# 15.net
KiCad netlist of a schematic drawn in EasyEDA Pro
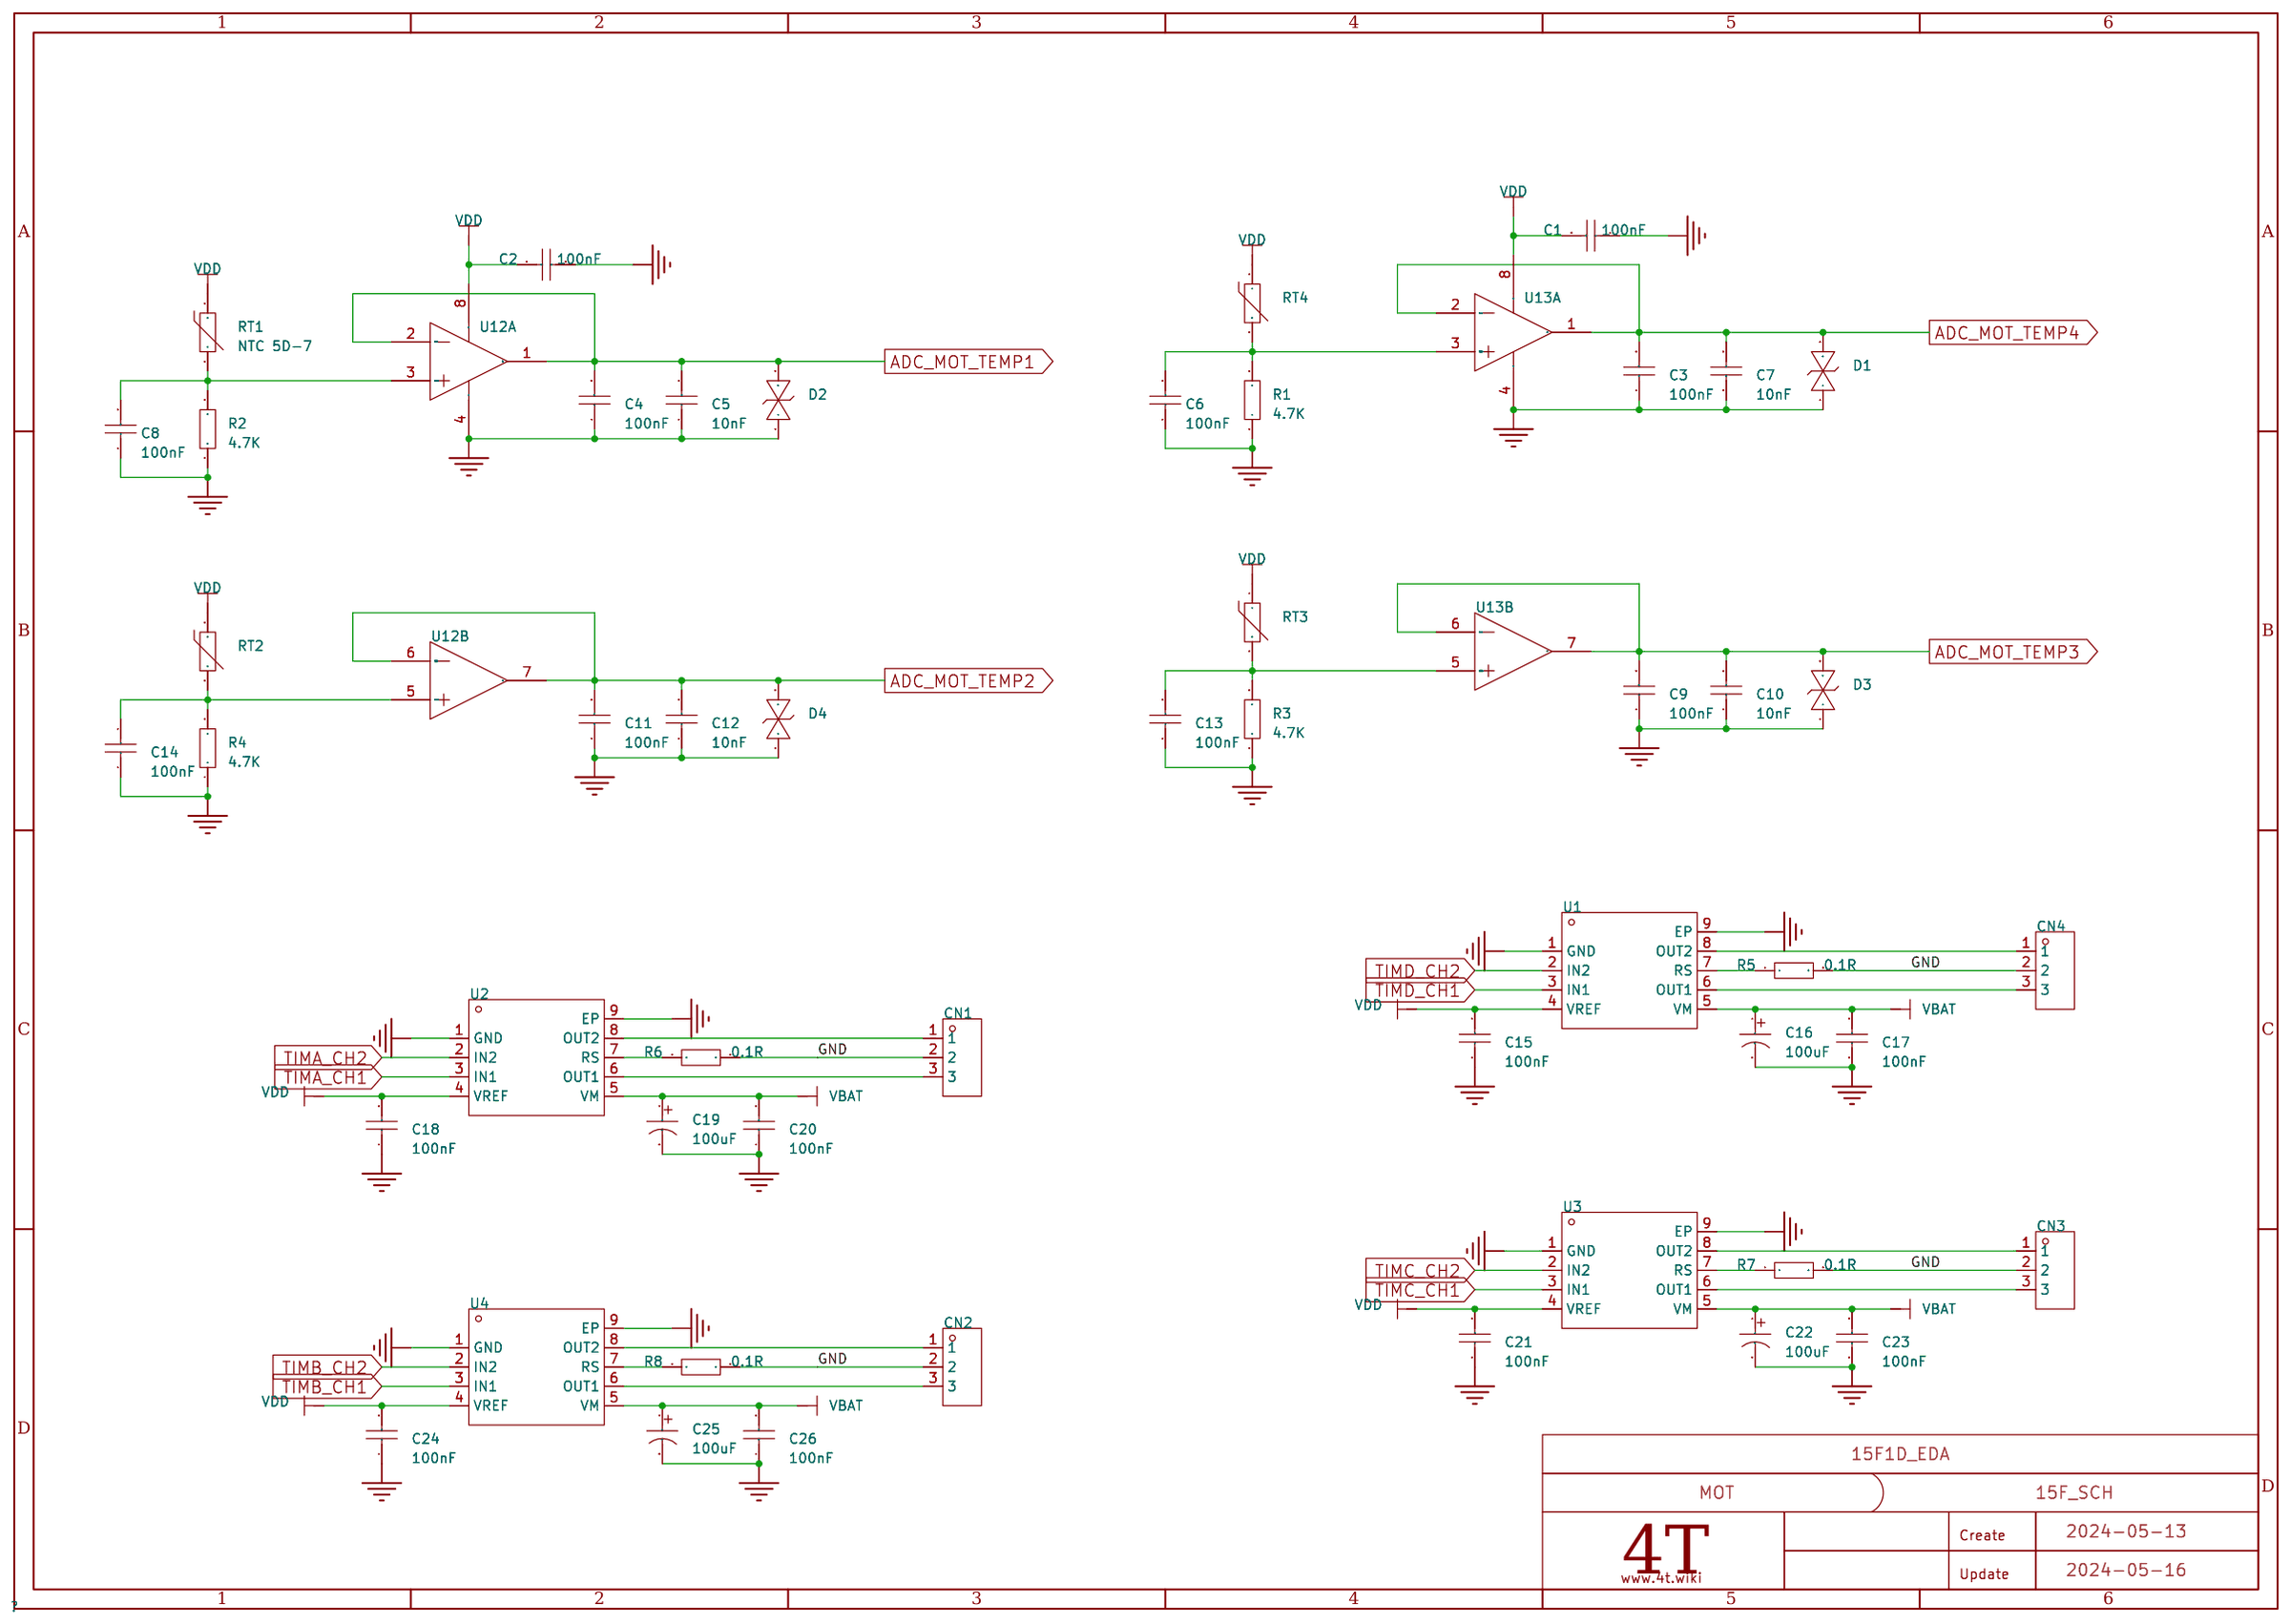
[diagram p0: MOT]
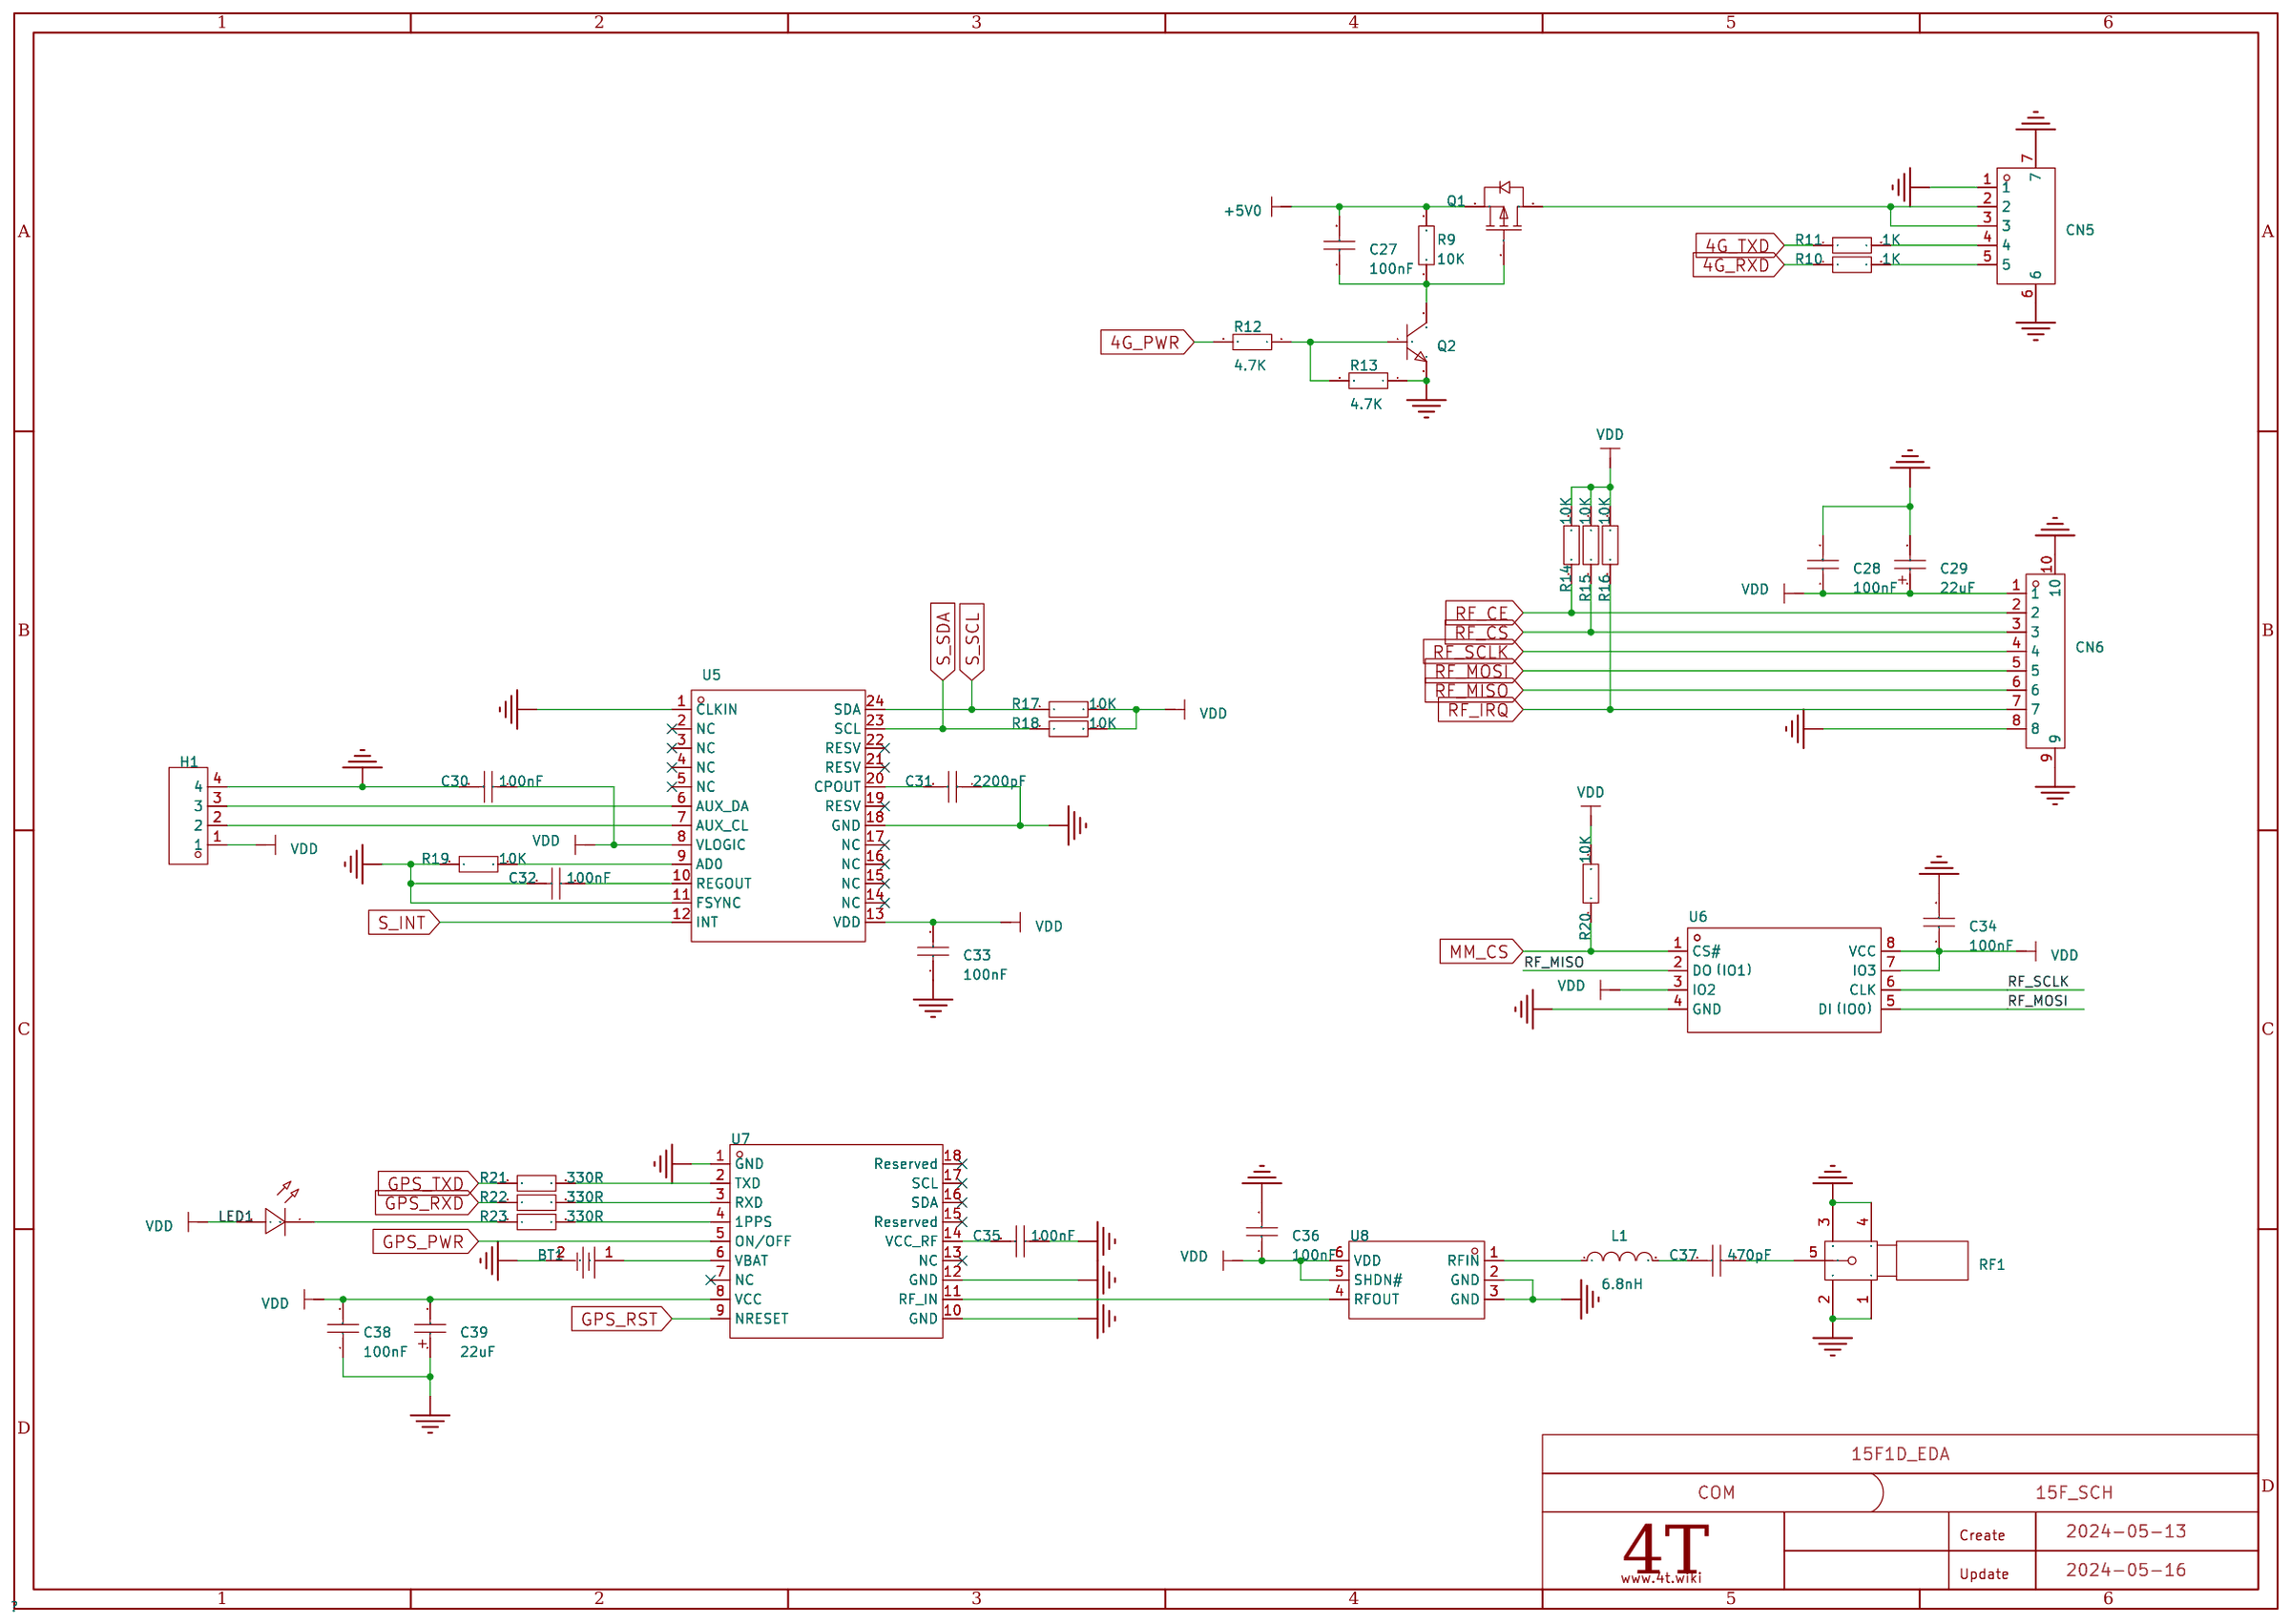
[diagram p1: COM]
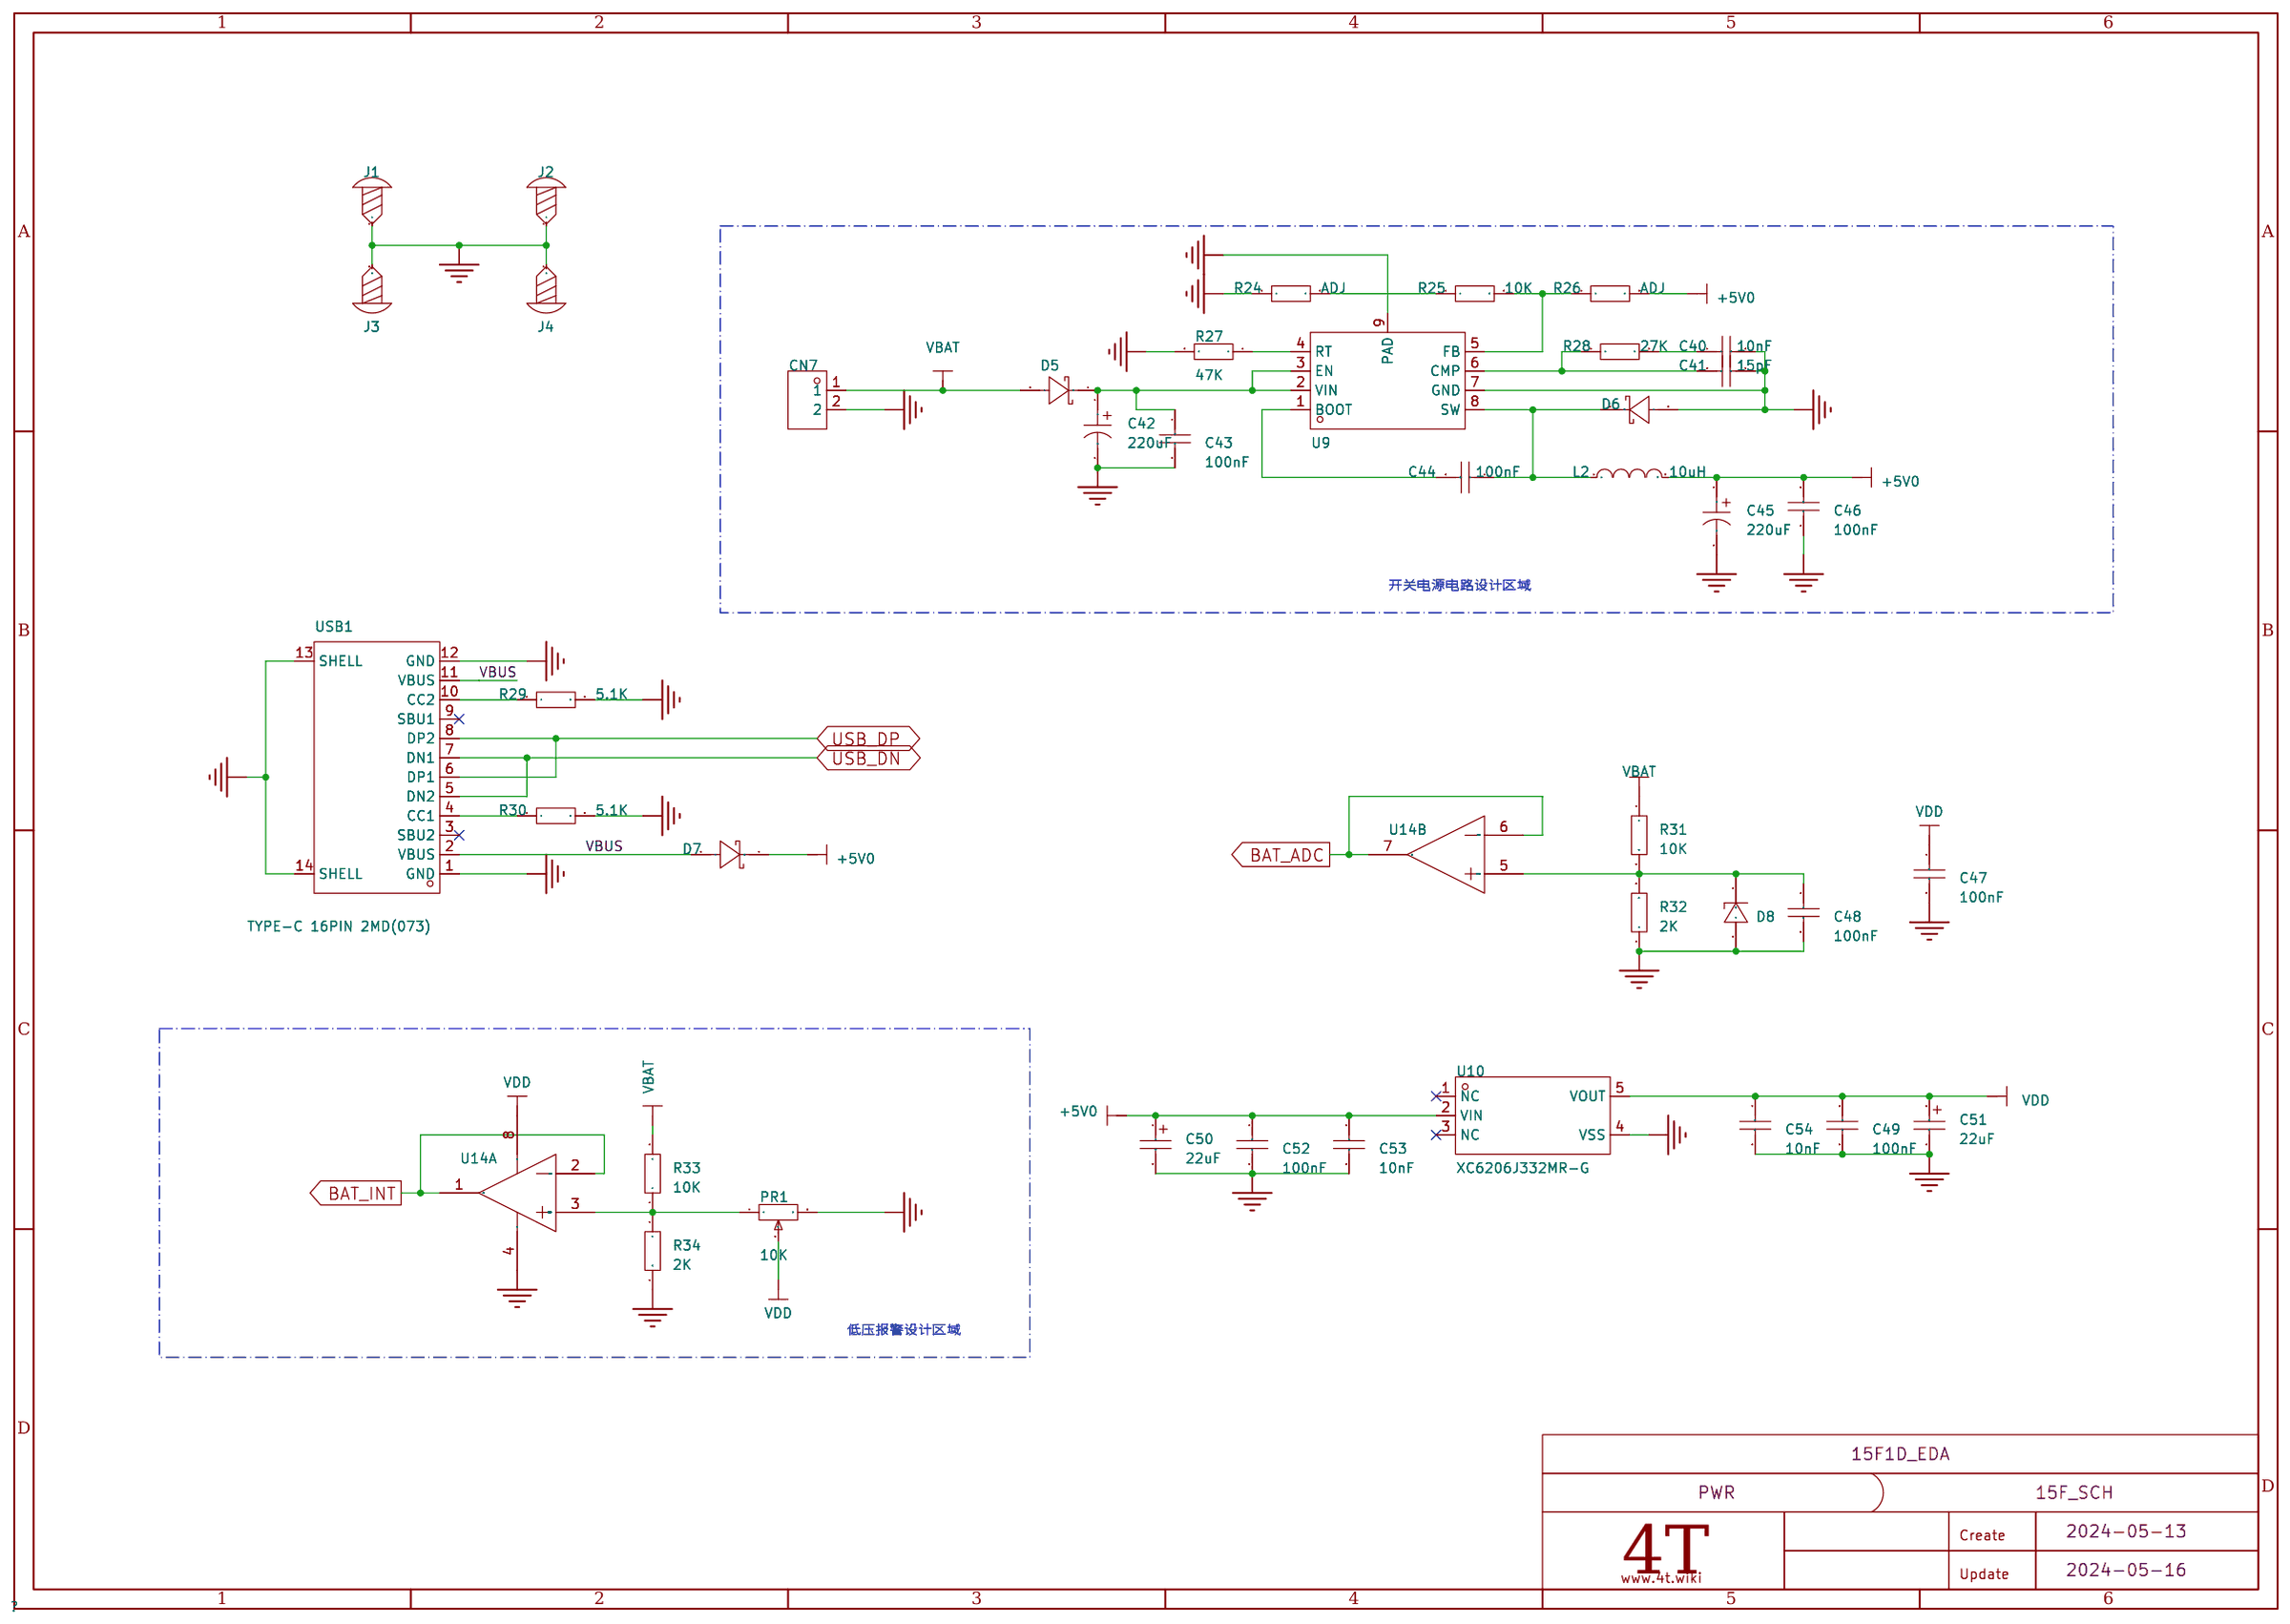
[diagram p2: PWR]
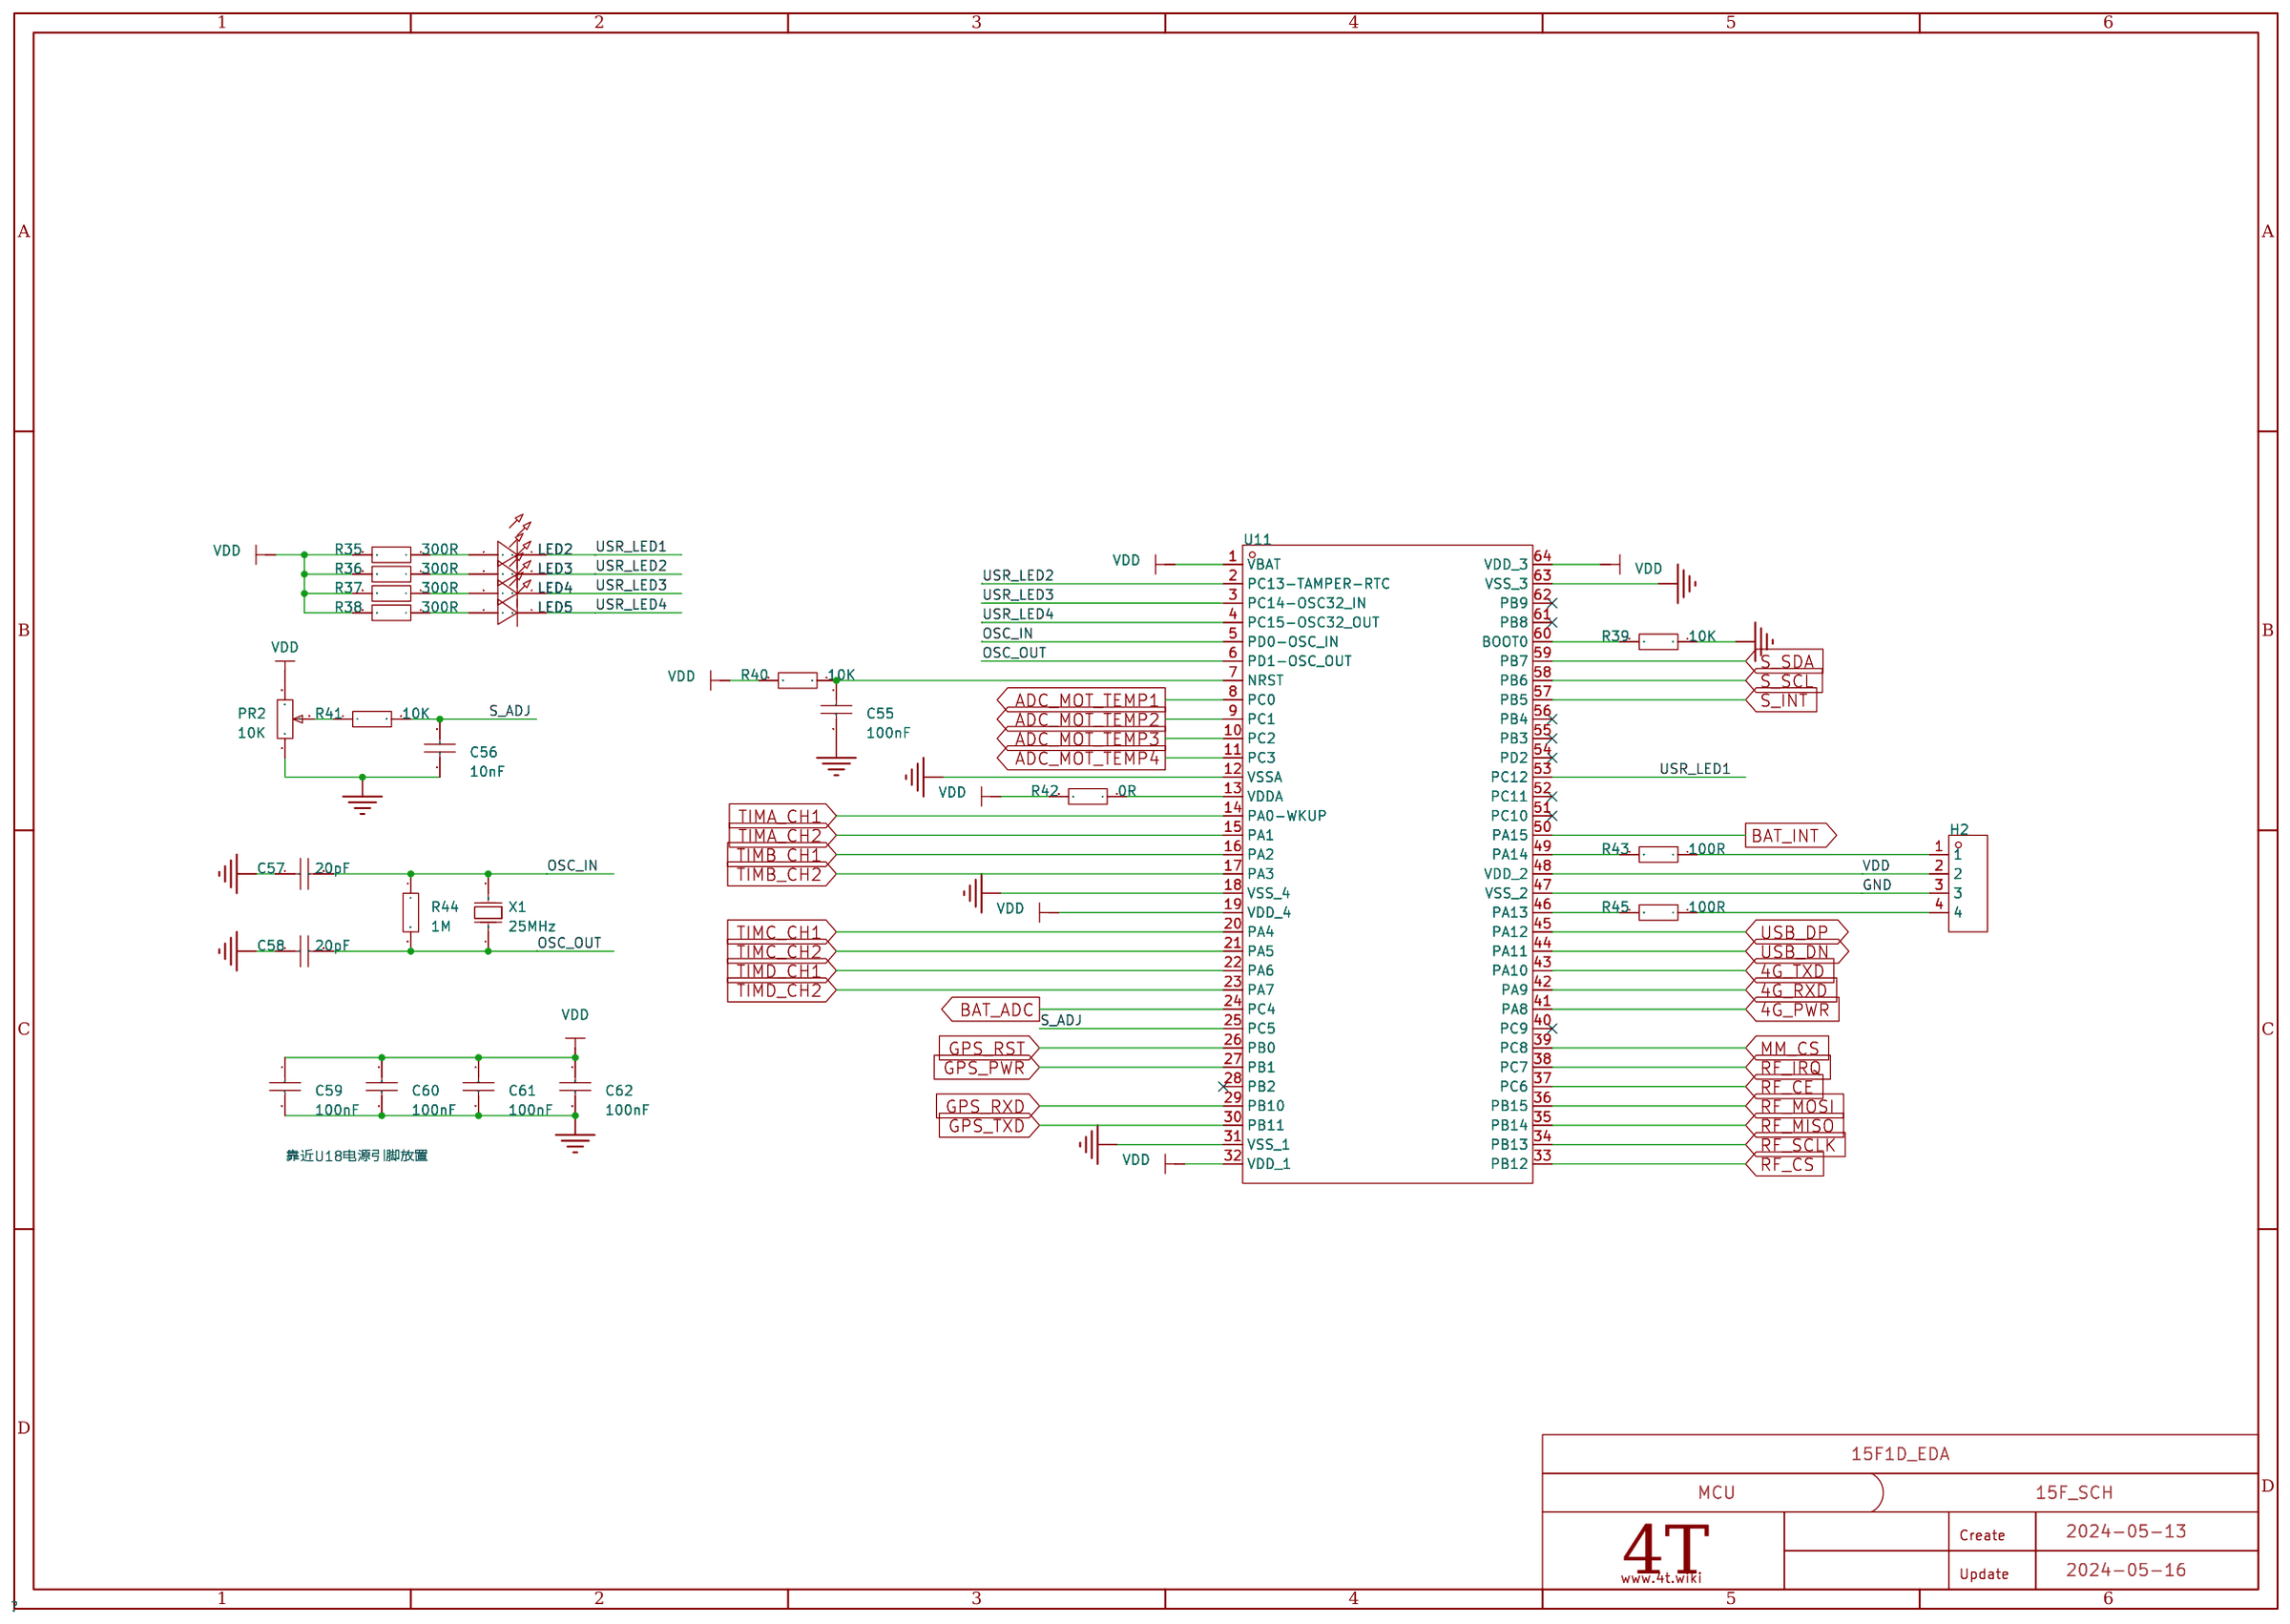
[diagram p3: MCU]

(export (version "E")
  (design (tool "Eeschema 10.0.6"))
  (components
    (comp (ref "C1")
      (value "100nF")
      (footprint "easyedapro:C0805")
      (description "容值:100nF;精度:±10%;额定电压:100V;材质(温度系数):X7R;")
      (fields
        (field (name "Manufacturer Part") "CC0805KKX7R0BB104")
        (field (name "Manufacturer") "YAGEO(国巨)")
      )
      (libsource (lib "easyedapro") (part "CC0805KKX7R0BB104"))
    )
    (comp (ref "C2")
      (value "100nF")
      (footprint "easyedapro:C0805")
      (description "容值:100nF;精度:±10%;额定电压:100V;材质(温度系数):X7R;")
      (fields
        (field (name "Manufacturer Part") "CC0805KKX7R0BB104")
        (field (name "Manufacturer") "YAGEO(国巨)")
      )
      (libsource (lib "easyedapro") (part "CC0805KKX7R0BB104"))
    )
    (comp (ref "C3")
      (value "100nF")
      (footprint "easyedapro:C0805")
      (description "容值:100nF;精度:±10%;额定电压:100V;材质(温度系数):X7R;")
      (fields
        (field (name "Manufacturer Part") "CC0805KKX7R0BB104")
        (field (name "Manufacturer") "YAGEO(国巨)")
      )
      (libsource (lib "easyedapro") (part "CC0805KKX7R0BB104"))
    )
    (comp (ref "C4")
      (value "100nF")
      (footprint "easyedapro:C0805")
      (description "容值:100nF;精度:±10%;额定电压:100V;材质(温度系数):X7R;")
      (fields
        (field (name "Manufacturer Part") "CC0805KKX7R0BB104")
        (field (name "Manufacturer") "YAGEO(国巨)")
      )
      (libsource (lib "easyedapro") (part "CC0805KKX7R0BB104"))
    )
    (comp (ref "C5")
      (value "10nF")
      (footprint "easyedapro:C0805")
      (description "容值:100nF;精度:±10%;额定电压:100V;材质(温度系数):X7R;")
      (fields
        (field (name "Manufacturer Part") "CC0805KKX7R0BB104")
        (field (name "Manufacturer") "YAGEO(国巨)")
      )
      (libsource (lib "easyedapro") (part "CC0805KKX7R0BB104"))
    )
    (comp (ref "C6")
      (value "100nF")
      (footprint "easyedapro:C0805")
      (description "容值:100nF;精度:±10%;额定电压:100V;材质(温度系数):X7R;")
      (fields
        (field (name "Manufacturer Part") "CC0805KKX7R0BB104")
        (field (name "Manufacturer") "YAGEO(国巨)")
      )
      (libsource (lib "easyedapro") (part "CC0805KKX7R0BB104"))
    )
    (comp (ref "C7")
      (value "10nF")
      (footprint "easyedapro:C0805")
      (description "容值:100nF;精度:±10%;额定电压:100V;材质(温度系数):X7R;")
      (fields
        (field (name "Manufacturer Part") "CC0805KKX7R0BB104")
        (field (name "Manufacturer") "YAGEO(国巨)")
      )
      (libsource (lib "easyedapro") (part "CC0805KKX7R0BB104"))
    )
    (comp (ref "C8")
      (value "100nF")
      (footprint "easyedapro:C0805")
      (description "容值:100nF;精度:±10%;额定电压:100V;材质(温度系数):X7R;")
      (fields
        (field (name "Manufacturer Part") "CC0805KKX7R0BB104")
        (field (name "Manufacturer") "YAGEO(国巨)")
      )
      (libsource (lib "easyedapro") (part "CC0805KKX7R0BB104"))
    )
    (comp (ref "C9")
      (value "100nF")
      (footprint "easyedapro:C0805")
      (description "容值:100nF;精度:±10%;额定电压:100V;材质(温度系数):X7R;")
      (fields
        (field (name "Manufacturer Part") "CC0805KKX7R0BB104")
        (field (name "Manufacturer") "YAGEO(国巨)")
      )
      (libsource (lib "easyedapro") (part "CC0805KKX7R0BB104"))
    )
    (comp (ref "C10")
      (value "10nF")
      (footprint "easyedapro:C0805")
      (description "容值:100nF;精度:±10%;额定电压:100V;材质(温度系数):X7R;")
      (fields
        (field (name "Manufacturer Part") "CC0805KKX7R0BB104")
        (field (name "Manufacturer") "YAGEO(国巨)")
      )
      (libsource (lib "easyedapro") (part "CC0805KKX7R0BB104"))
    )
    (comp (ref "C11")
      (value "100nF")
      (footprint "easyedapro:C0805")
      (description "容值:100nF;精度:±10%;额定电压:100V;材质(温度系数):X7R;")
      (fields
        (field (name "Manufacturer Part") "CC0805KKX7R0BB104")
        (field (name "Manufacturer") "YAGEO(国巨)")
      )
      (libsource (lib "easyedapro") (part "CC0805KKX7R0BB104"))
    )
    (comp (ref "C12")
      (value "10nF")
      (footprint "easyedapro:C0805")
      (description "容值:100nF;精度:±10%;额定电压:100V;材质(温度系数):X7R;")
      (fields
        (field (name "Manufacturer Part") "CC0805KKX7R0BB104")
        (field (name "Manufacturer") "YAGEO(国巨)")
      )
      (libsource (lib "easyedapro") (part "CC0805KKX7R0BB104"))
    )
    (comp (ref "C13")
      (value "100nF")
      (footprint "easyedapro:C0805")
      (description "容值:100nF;精度:±10%;额定电压:100V;材质(温度系数):X7R;")
      (fields
        (field (name "Manufacturer Part") "CC0805KKX7R0BB104")
        (field (name "Manufacturer") "YAGEO(国巨)")
      )
      (libsource (lib "easyedapro") (part "CC0805KKX7R0BB104"))
    )
    (comp (ref "C14")
      (value "100nF")
      (footprint "easyedapro:C0805")
      (description "容值:100nF;精度:±10%;额定电压:100V;材质(温度系数):X7R;")
      (fields
        (field (name "Manufacturer Part") "CC0805KKX7R0BB104")
        (field (name "Manufacturer") "YAGEO(国巨)")
      )
      (libsource (lib "easyedapro") (part "CC0805KKX7R0BB104"))
    )
    (comp (ref "C15")
      (value "100nF")
      (footprint "easyedapro:C0805")
      (description "容值:100nF;精度:±10%;额定电压:100V;材质(温度系数):X7R;")
      (fields
        (field (name "Manufacturer Part") "CC0805KKX7R0BB104")
        (field (name "Manufacturer") "YAGEO(国巨)")
      )
      (libsource (lib "easyedapro") (part "CC0805KKX7R0BB104"))
    )
    (comp (ref "C16")
      (value "100uF")
      (footprint "easyedapro:CAP-SMD_BD6.3-L6.6-W6.6-LS7.2-FD")
      (description "容值:100uF;精度:±20%;额定电压:16V;纹波电流:-;等效串联电阻:-;")
      (fields (field (name "Manufacturer Part") "RVT1C101M0605") (field (name "Manufacturer") "HONOR(荣誉)"))
      (libsource (lib "easyedapro") (part "RVT1C101M0605"))
    )
    (comp (ref "C17")
      (value "100nF")
      (footprint "easyedapro:C0805")
      (description "容值:100nF;精度:±10%;额定电压:100V;材质(温度系数):X7R;")
      (fields
        (field (name "Manufacturer Part") "CC0805KKX7R0BB104")
        (field (name "Manufacturer") "YAGEO(国巨)")
      )
      (libsource (lib "easyedapro") (part "CC0805KKX7R0BB104"))
    )
    (comp (ref "C18")
      (value "100nF")
      (footprint "easyedapro:C0805")
      (description "容值:100nF;精度:±10%;额定电压:100V;材质(温度系数):X7R;")
      (fields
        (field (name "Manufacturer Part") "CC0805KKX7R0BB104")
        (field (name "Manufacturer") "YAGEO(国巨)")
      )
      (libsource (lib "easyedapro") (part "CC0805KKX7R0BB104"))
    )
    (comp (ref "C19")
      (value "100uF")
      (footprint "easyedapro:CAP-SMD_BD6.3-L6.6-W6.6-LS7.2-FD")
      (description "容值:100uF;精度:±20%;额定电压:16V;纹波电流:-;等效串联电阻:-;")
      (fields (field (name "Manufacturer Part") "RVT1C101M0605") (field (name "Manufacturer") "HONOR(荣誉)"))
      (libsource (lib "easyedapro") (part "RVT1C101M0605"))
    )
    (comp (ref "C20")
      (value "100nF")
      (footprint "easyedapro:C0805")
      (description "容值:100nF;精度:±10%;额定电压:100V;材质(温度系数):X7R;")
      (fields
        (field (name "Manufacturer Part") "CC0805KKX7R0BB104")
        (field (name "Manufacturer") "YAGEO(国巨)")
      )
      (libsource (lib "easyedapro") (part "CC0805KKX7R0BB104"))
    )
    (comp (ref "C21")
      (value "100nF")
      (footprint "easyedapro:C0805")
      (description "容值:100nF;精度:±10%;额定电压:100V;材质(温度系数):X7R;")
      (fields
        (field (name "Manufacturer Part") "CC0805KKX7R0BB104")
        (field (name "Manufacturer") "YAGEO(国巨)")
      )
      (libsource (lib "easyedapro") (part "CC0805KKX7R0BB104"))
    )
    (comp (ref "C22")
      (value "100uF")
      (footprint "easyedapro:CAP-SMD_BD6.3-L6.6-W6.6-LS7.2-FD")
      (description "容值:100uF;精度:±20%;额定电压:16V;纹波电流:-;等效串联电阻:-;")
      (fields (field (name "Manufacturer Part") "RVT1C101M0605") (field (name "Manufacturer") "HONOR(荣誉)"))
      (libsource (lib "easyedapro") (part "RVT1C101M0605"))
    )
    (comp (ref "C23")
      (value "100nF")
      (footprint "easyedapro:C0805")
      (description "容值:100nF;精度:±10%;额定电压:100V;材质(温度系数):X7R;")
      (fields
        (field (name "Manufacturer Part") "CC0805KKX7R0BB104")
        (field (name "Manufacturer") "YAGEO(国巨)")
      )
      (libsource (lib "easyedapro") (part "CC0805KKX7R0BB104"))
    )
    (comp (ref "C24")
      (value "100nF")
      (footprint "easyedapro:C0805")
      (description "容值:100nF;精度:±10%;额定电压:100V;材质(温度系数):X7R;")
      (fields
        (field (name "Manufacturer Part") "CC0805KKX7R0BB104")
        (field (name "Manufacturer") "YAGEO(国巨)")
      )
      (libsource (lib "easyedapro") (part "CC0805KKX7R0BB104"))
    )
    (comp (ref "C25")
      (value "100uF")
      (footprint "easyedapro:CAP-SMD_BD6.3-L6.6-W6.6-LS7.2-FD")
      (description "容值:100uF;精度:±20%;额定电压:16V;纹波电流:-;等效串联电阻:-;")
      (fields (field (name "Manufacturer Part") "RVT1C101M0605") (field (name "Manufacturer") "HONOR(荣誉)"))
      (libsource (lib "easyedapro") (part "RVT1C101M0605"))
    )
    (comp (ref "C26")
      (value "100nF")
      (footprint "easyedapro:C0805")
      (description "容值:100nF;精度:±10%;额定电压:100V;材质(温度系数):X7R;")
      (fields
        (field (name "Manufacturer Part") "CC0805KKX7R0BB104")
        (field (name "Manufacturer") "YAGEO(国巨)")
      )
      (libsource (lib "easyedapro") (part "CC0805KKX7R0BB104"))
    )
    (comp (ref "CN1")
      (value "2.54-1*3P")
      (footprint "easyedapro:CONN-TH_C722693")
      (description "插针结构:1x3P;间距:2.5mm;安装方式:直插;参考系列:-;总PIN数:3P;排数:1;每排PIN数:3;行距:-;额定电流:2A;工作温度范围:-25°C~+85°C;")
      (fields (field (name "Manufacturer") "CAX(创都)"))
      (libsource (lib "easyedapro") (part "2.54-1*3P"))
    )
    (comp (ref "CN2")
      (value "2.54-1*3P")
      (footprint "easyedapro:CONN-TH_C722693")
      (description "插针结构:1x3P;间距:2.5mm;安装方式:直插;参考系列:-;总PIN数:3P;排数:1;每排PIN数:3;行距:-;额定电流:2A;工作温度范围:-25°C~+85°C;")
      (fields (field (name "Manufacturer") "CAX(创都)"))
      (libsource (lib "easyedapro") (part "2.54-1*3P"))
    )
    (comp (ref "CN3")
      (value "2.54-1*3P")
      (footprint "easyedapro:CONN-TH_C722693")
      (description "插针结构:1x3P;间距:2.5mm;安装方式:直插;参考系列:-;总PIN数:3P;排数:1;每排PIN数:3;行距:-;额定电流:2A;工作温度范围:-25°C~+85°C;")
      (fields (field (name "Manufacturer") "CAX(创都)"))
      (libsource (lib "easyedapro") (part "2.54-1*3P"))
    )
    (comp (ref "CN4")
      (value "2.54-1*3P")
      (footprint "easyedapro:CONN-TH_C722693")
      (description "插针结构:1x3P;间距:2.5mm;安装方式:直插;参考系列:-;总PIN数:3P;排数:1;每排PIN数:3;行距:-;额定电流:2A;工作温度范围:-25°C~+85°C;")
      (fields (field (name "Manufacturer") "CAX(创都)"))
      (libsource (lib "easyedapro") (part "2.54-1*3P"))
    )
    (comp (ref "D1")
      (value "H3V3LD5B")
      (footprint "easyedapro:SOD-523F_L1.7-W0.9-LS1.7-BI")
      (description "极性:双向;反向截止电压(Vrwm):3.3V;最大钳位电压:12V;峰值脉冲电流(Ipp)@10/1000us:8A;峰值脉冲功率(Ppp)@10/1000us:100W;击穿电压:6.5V;")
      (fields (field (name "Manufacturer") "宏迦橙"))
      (libsource (lib "easyedapro") (part "H3V3LD5B"))
    )
    (comp (ref "D2")
      (value "H3V3LD5B")
      (footprint "easyedapro:SOD-523F_L1.7-W0.9-LS1.7-BI")
      (description "极性:双向;反向截止电压(Vrwm):3.3V;最大钳位电压:12V;峰值脉冲电流(Ipp)@10/1000us:8A;峰值脉冲功率(Ppp)@10/1000us:100W;击穿电压:6.5V;")
      (fields (field (name "Manufacturer") "宏迦橙"))
      (libsource (lib "easyedapro") (part "H3V3LD5B"))
    )
    (comp (ref "D3")
      (value "H3V3LD5B")
      (footprint "easyedapro:SOD-523F_L1.7-W0.9-LS1.7-BI")
      (description "极性:双向;反向截止电压(Vrwm):3.3V;最大钳位电压:12V;峰值脉冲电流(Ipp)@10/1000us:8A;峰值脉冲功率(Ppp)@10/1000us:100W;击穿电压:6.5V;")
      (fields (field (name "Manufacturer") "宏迦橙"))
      (libsource (lib "easyedapro") (part "H3V3LD5B"))
    )
    (comp (ref "D4")
      (value "H3V3LD5B")
      (footprint "easyedapro:SOD-523F_L1.7-W0.9-LS1.7-BI")
      (description "极性:双向;反向截止电压(Vrwm):3.3V;最大钳位电压:12V;峰值脉冲电流(Ipp)@10/1000us:8A;峰值脉冲功率(Ppp)@10/1000us:100W;击穿电压:6.5V;")
      (fields (field (name "Manufacturer") "宏迦橙"))
      (libsource (lib "easyedapro") (part "H3V3LD5B"))
    )
    (comp (ref "R1") (value "4.7K") (footprint "easyedapro:R0603") (libsource (lib "easyedapro") (part "电阻")))
    (comp (ref "R2") (value "4.7K") (footprint "easyedapro:R0603") (libsource (lib "easyedapro") (part "电阻")))
    (comp (ref "R3") (value "4.7K") (footprint "easyedapro:R0603") (libsource (lib "easyedapro") (part "电阻")))
    (comp (ref "R4") (value "4.7K") (footprint "easyedapro:R0603") (libsource (lib "easyedapro") (part "电阻")))
    (comp (ref "R5") (value "0.1R") (footprint "easyedapro:R0603") (libsource (lib "easyedapro") (part "电阻")))
    (comp (ref "R6") (value "0.1R") (footprint "easyedapro:R0603") (libsource (lib "easyedapro") (part "电阻")))
    (comp (ref "R7") (value "0.1R") (footprint "easyedapro:R0603") (libsource (lib "easyedapro") (part "电阻")))
    (comp (ref "R8") (value "0.1R") (footprint "easyedapro:R0603") (libsource (lib "easyedapro") (part "电阻")))
    (comp (ref "RT1")
      (value "NTC 5D-7")
      (footprint "easyedapro:RES-TH_L8.5-W5.5-P5.00-D0.6-S5.50")
      (description "阻值(25°C):5Ω;B值(25°C/50°C):-;电阻精度:-;功率:-;B值精度:-;最大稳态电流(25°C):2A;")
      (fields (field (name "Manufacturer") "RUILON(瑞隆源)"))
      (libsource (lib "easyedapro") (part "NTC 5D-7"))
    )
    (comp (ref "RT2")
      (value "NTC 5D-7")
      (footprint "easyedapro:RES-TH_L8.5-W5.5-P5.00-D0.6-S5.50")
      (description "阻值(25°C):5Ω;B值(25°C/50°C):-;电阻精度:-;功率:-;B值精度:-;最大稳态电流(25°C):2A;")
      (fields (field (name "Manufacturer") "RUILON(瑞隆源)"))
      (libsource (lib "easyedapro") (part "NTC 5D-7"))
    )
    (comp (ref "RT3")
      (value "NTC 5D-7")
      (footprint "easyedapro:RES-TH_L8.5-W5.5-P5.00-D0.6-S5.50")
      (description "阻值(25°C):5Ω;B值(25°C/50°C):-;电阻精度:-;功率:-;B值精度:-;最大稳态电流(25°C):2A;")
      (fields (field (name "Manufacturer") "RUILON(瑞隆源)"))
      (libsource (lib "easyedapro") (part "NTC 5D-7"))
    )
    (comp (ref "RT4")
      (value "NTC 5D-7")
      (footprint "easyedapro:RES-TH_L8.5-W5.5-P5.00-D0.6-S5.50")
      (description "阻值(25°C):5Ω;B值(25°C/50°C):-;电阻精度:-;功率:-;B值精度:-;最大稳态电流(25°C):2A;")
      (fields (field (name "Manufacturer") "RUILON(瑞隆源)"))
      (libsource (lib "easyedapro") (part "NTC 5D-7"))
    )
    (comp (ref "U1")
      (value "TB67H450FNG,EL")
      (footprint "easyedapro:HSOP-8_L5.0-W4.0-P1.27-LS6.2-BL-EP")
      (description "驱动电机类型:有刷直流电机;输出电流:3.5A;")
      (fields (field (name "Manufacturer") "TOSHIBA(东芝)"))
      (libsource (lib "easyedapro") (part "TB67H450FNG,EL"))
    )
    (comp (ref "U2")
      (value "TB67H450FNG,EL")
      (footprint "easyedapro:HSOP-8_L5.0-W4.0-P1.27-LS6.2-BL-EP")
      (description "驱动电机类型:有刷直流电机;输出电流:3.5A;")
      (fields (field (name "Manufacturer") "TOSHIBA(东芝)"))
      (libsource (lib "easyedapro") (part "TB67H450FNG,EL"))
    )
    (comp (ref "U3")
      (value "TB67H450FNG,EL")
      (footprint "easyedapro:HSOP-8_L5.0-W4.0-P1.27-LS6.2-BL-EP")
      (description "驱动电机类型:有刷直流电机;输出电流:3.5A;")
      (fields (field (name "Manufacturer") "TOSHIBA(东芝)"))
      (libsource (lib "easyedapro") (part "TB67H450FNG,EL"))
    )
    (comp (ref "U4")
      (value "TB67H450FNG,EL")
      (footprint "easyedapro:HSOP-8_L5.0-W4.0-P1.27-LS6.2-BL-EP")
      (description "驱动电机类型:有刷直流电机;输出电流:3.5A;")
      (fields (field (name "Manufacturer") "TOSHIBA(东芝)"))
      (libsource (lib "easyedapro") (part "TB67H450FNG,EL"))
    )
    (comp (ref "U12")
      (value "GS8552-SR")
      (footprint "easyedapro:SOIC-8_L4.9-W3.9-P1.27-LS6.0-BL")
      (description "放大器数:双路;增益带宽积(GBP):1.8MHz;压摆率(SR):0.95V/us;")
      (fields (field (name "Manufacturer") "Gainsil(聚洵)"))
      (libsource (lib "easyedapro") (part "GS8552-SR"))
    )
    (comp (ref "U13")
      (value "GS8552-SR")
      (footprint "easyedapro:SOIC-8_L4.9-W3.9-P1.27-LS6.0-BL")
      (description "放大器数:双路;增益带宽积(GBP):1.8MHz;压摆率(SR):0.95V/us;")
      (fields (field (name "Manufacturer") "Gainsil(聚洵)"))
      (libsource (lib "easyedapro") (part "GS8552-SR"))
    )
    (comp (ref "BT1")
      (value "CR1220-A")
      (footprint "easyedapro:BAT-SMD_CR1220-2")
      (libsource (lib "easyedapro") (part "CR1220-A"))
    )
    (comp (ref "C27")
      (value "100nF")
      (footprint "easyedapro:C0805")
      (description "容值:100nF;精度:±10%;额定电压:100V;材质(温度系数):X7R;")
      (fields
        (field (name "Manufacturer Part") "CC0805KKX7R0BB104")
        (field (name "Manufacturer") "YAGEO(国巨)")
      )
      (libsource (lib "easyedapro") (part "CC0805KKX7R0BB104"))
    )
    (comp (ref "C28")
      (value "100nF")
      (footprint "easyedapro:C0805")
      (description "容值:100nF;精度:±10%;额定电压:100V;材质(温度系数):X7R;")
      (fields
        (field (name "Manufacturer Part") "CC0805KKX7R0BB104")
        (field (name "Manufacturer") "YAGEO(国巨)")
      )
      (libsource (lib "easyedapro") (part "CC0805KKX7R0BB104"))
    )
    (comp (ref "C29")
      (value "22uF")
      (footprint "easyedapro:CASE-A_3216")
      (description "容值:22uF;精度:±10%;额定电压:10V;等效串联电阻:3Ω@100kHz;")
      (fields (field (name "Manufacturer Part") "TAJA226K010RNJ") (field (name "Manufacturer") "Kyocera AVX"))
      (libsource (lib "easyedapro") (part "TAJA226K010RNJ"))
    )
    (comp (ref "C30")
      (value "100nF")
      (footprint "easyedapro:C0805")
      (description "容值:100nF;精度:±10%;额定电压:100V;材质(温度系数):X7R;")
      (fields
        (field (name "Manufacturer Part") "CC0805KKX7R0BB104")
        (field (name "Manufacturer") "YAGEO(国巨)")
      )
      (libsource (lib "easyedapro") (part "CC0805KKX7R0BB104"))
    )
    (comp (ref "C31")
      (value "2200pF")
      (footprint "easyedapro:C0805")
      (description "容值:100nF;精度:±10%;额定电压:100V;材质(温度系数):X7R;")
      (fields
        (field (name "Manufacturer Part") "CC0805KKX7R0BB104")
        (field (name "Manufacturer") "YAGEO(国巨)")
      )
      (libsource (lib "easyedapro") (part "CC0805KKX7R0BB104"))
    )
    (comp (ref "C32")
      (value "100nF")
      (footprint "easyedapro:C0805")
      (description "容值:100nF;精度:±10%;额定电压:100V;材质(温度系数):X7R;")
      (fields
        (field (name "Manufacturer Part") "CC0805KKX7R0BB104")
        (field (name "Manufacturer") "YAGEO(国巨)")
      )
      (libsource (lib "easyedapro") (part "CC0805KKX7R0BB104"))
    )
    (comp (ref "C33")
      (value "100nF")
      (footprint "easyedapro:C0805")
      (description "容值:100nF;精度:±10%;额定电压:100V;材质(温度系数):X7R;")
      (fields
        (field (name "Manufacturer Part") "CC0805KKX7R0BB104")
        (field (name "Manufacturer") "YAGEO(国巨)")
      )
      (libsource (lib "easyedapro") (part "CC0805KKX7R0BB104"))
    )
    (comp (ref "C34")
      (value "100nF")
      (footprint "easyedapro:C0805")
      (description "容值:100nF;精度:±10%;额定电压:100V;材质(温度系数):X7R;")
      (fields
        (field (name "Manufacturer Part") "CC0805KKX7R0BB104")
        (field (name "Manufacturer") "YAGEO(国巨)")
      )
      (libsource (lib "easyedapro") (part "CC0805KKX7R0BB104"))
    )
    (comp (ref "C35")
      (value "100nF")
      (footprint "easyedapro:C0805")
      (description "容值:100nF;精度:±10%;额定电压:100V;材质(温度系数):X7R;")
      (fields
        (field (name "Manufacturer Part") "CC0805KKX7R0BB104")
        (field (name "Manufacturer") "YAGEO(国巨)")
      )
      (libsource (lib "easyedapro") (part "CC0805KKX7R0BB104"))
    )
    (comp (ref "C36")
      (value "100nF")
      (footprint "easyedapro:C0805")
      (description "容值:100nF;精度:±10%;额定电压:100V;材质(温度系数):X7R;")
      (fields
        (field (name "Manufacturer Part") "CC0805KKX7R0BB104")
        (field (name "Manufacturer") "YAGEO(国巨)")
      )
      (libsource (lib "easyedapro") (part "CC0805KKX7R0BB104"))
    )
    (comp (ref "C37")
      (value "470pF")
      (footprint "easyedapro:C0805")
      (description "容值:100nF;精度:±10%;额定电压:100V;材质(温度系数):X7R;")
      (fields
        (field (name "Manufacturer Part") "CC0805KKX7R0BB104")
        (field (name "Manufacturer") "YAGEO(国巨)")
      )
      (libsource (lib "easyedapro") (part "CC0805KKX7R0BB104"))
    )
    (comp (ref "C38")
      (value "100nF")
      (footprint "easyedapro:C0805")
      (description "容值:100nF;精度:±10%;额定电压:100V;材质(温度系数):X7R;")
      (fields
        (field (name "Manufacturer Part") "CC0805KKX7R0BB104")
        (field (name "Manufacturer") "YAGEO(国巨)")
      )
      (libsource (lib "easyedapro") (part "CC0805KKX7R0BB104"))
    )
    (comp (ref "C39")
      (value "22uF")
      (footprint "easyedapro:CASE-A_3216")
      (description "容值:22uF;精度:±10%;额定电压:10V;等效串联电阻:3Ω@100kHz;")
      (fields (field (name "Manufacturer Part") "TAJA226K010RNJ") (field (name "Manufacturer") "Kyocera AVX"))
      (libsource (lib "easyedapro") (part "TAJA226K010RNJ"))
    )
    (comp (ref "CN5")
      (value "ZX-XH2.54-5PWT")
      (footprint "easyedapro:CONN-SMD_5P-P2.54_MEGASTAR_ZX-XH2.54-5PWT")
      (fields (field (name "Manufacturer") "Megastar(兆星)"))
      (libsource (lib "easyedapro") (part "ZX-XH2.54-5PWT"))
    )
    (comp (ref "CN6")
      (value "2.54-8P WT")
      (footprint "easyedapro:CONN-SMD_8P-P2.50_2.54-8P-WT")
      (description "插针结构:1x8P;间距:2.54mm;安装方式:卧贴;参考系列:XH;总PIN数:8P;排数:1;每排PIN数:8;额定电流:3A;工作温度范围:-25°C~+85°C;")
      (fields (field (name "Manufacturer") "SHOU HAN(首韩)"))
      (libsource (lib "easyedapro") (part "2.54-8P WT"))
    )
    (comp (ref "H1")
      (value "~")
      (footprint "easyedapro:HDR-TH_4P-P2.54-V-F")
      (libsource (lib "easyedapro") (part "2.54-1*4P母"))
    )
    (comp (ref "L1")
      (value "6.8nH")
      (footprint "easyedapro:L0805")
      (description "电感值:6.8nH;精度:±5%;额定电流:600mA;饱和电流(Isat):-;直流电阻(DCR):110mΩ;")
      (fields
        (field (name "Manufacturer Part") "BKW0805UC6N8JGT")
        (field (name "Manufacturer") "FH-BK(风华邦科)")
      )
      (libsource (lib "easyedapro") (part "BKW0805UC6N8JGT"))
    )
    (comp (ref "LED1")
      (value "~")
      (footprint "easyedapro:LED_0805")
      (libsource (lib "easyedapro") (part "LED_G"))
    )
    (comp (ref "Q1")
      (value "AO3401A")
      (footprint "easyedapro:SOT-23_L2.9-W1.3-P1.90-LS2.4-BR")
      (fields (field (name "Manufacturer") "AOS"))
      (libsource (lib "easyedapro") (part "AO3401A"))
    )
    (comp (ref "Q2")
      (value "S8050 J3Y")
      (footprint "easyedapro:SOT-23-3_L3.0-W1.7-P0.95-LS2.9-BR")
      (description "晶体管类型:NPN;集电极电流(Ic):500mA;集射极击穿电压(Vceo):25V;功率(Pd):300mW;直流电流增益(hFE@Ic,Vce):200@50mA,1V;")
      (fields (field (name "Manufacturer") "CJ(江苏长电/长晶)"))
      (libsource (lib "easyedapro") (part "S8050_C2146"))
    )
    (comp (ref "R9") (value "10K") (footprint "easyedapro:R0603") (libsource (lib "easyedapro") (part "电阻")))
    (comp (ref "R10") (value "1K") (footprint "easyedapro:R0603") (libsource (lib "easyedapro") (part "电阻")))
    (comp (ref "R11") (value "1K") (footprint "easyedapro:R0603") (libsource (lib "easyedapro") (part "电阻")))
    (comp (ref "R12")
      (value "4.7K")
      (footprint "easyedapro:R0603")
      (libsource (lib "easyedapro") (part "电阻"))
    )
    (comp (ref "R13")
      (value "4.7K")
      (footprint "easyedapro:R0603")
      (libsource (lib "easyedapro") (part "电阻"))
    )
    (comp (ref "R14") (value "10K") (footprint "easyedapro:R0603") (libsource (lib "easyedapro") (part "电阻")))
    (comp (ref "R15") (value "10K") (footprint "easyedapro:R0603") (libsource (lib "easyedapro") (part "电阻")))
    (comp (ref "R16") (value "10K") (footprint "easyedapro:R0603") (libsource (lib "easyedapro") (part "电阻")))
    (comp (ref "R17") (value "10K") (footprint "easyedapro:R0603") (libsource (lib "easyedapro") (part "电阻")))
    (comp (ref "R18") (value "10K") (footprint "easyedapro:R0603") (libsource (lib "easyedapro") (part "电阻")))
    (comp (ref "R19") (value "10K") (footprint "easyedapro:R0603") (libsource (lib "easyedapro") (part "电阻")))
    (comp (ref "R20") (value "10K") (footprint "easyedapro:R0603") (libsource (lib "easyedapro") (part "电阻")))
    (comp (ref "R21")
      (value "330R")
      (footprint "easyedapro:R0603")
      (libsource (lib "easyedapro") (part "电阻"))
    )
    (comp (ref "R22")
      (value "330R")
      (footprint "easyedapro:R0603")
      (libsource (lib "easyedapro") (part "电阻"))
    )
    (comp (ref "R23")
      (value "330R")
      (footprint "easyedapro:R0603")
      (libsource (lib "easyedapro") (part "电阻"))
    )
    (comp (ref "RF1")
      (value "BWSMA-KWE-Z001")
      (footprint "easyedapro:SMA-TH_BWSMA-KWE-Z001")
      (fields (field (name "Manufacturer") "BAT WIRELESS(蝙蝠无线)"))
      (libsource (lib "easyedapro") (part "BWSMA-KWE-Z001"))
    )
    (comp (ref "U5")
      (value "MPU6050")
      (footprint "easyedapro:QFN-24_L4.0-W4.0-P0.50-BL")
      (libsource (lib "easyedapro") (part "MPU6050_C9900042518"))
    )
    (comp (ref "U6")
      (value "W25Q32JVSSIQ")
      (footprint "easyedapro:SOIC-8_L5.3-W5.3-P1.27-LS8.0-BL")
      (description "接口类型:SPI;存储容量:32Mbit;")
      (fields (field (name "Manufacturer") "WINBOND(华邦)"))
      (libsource (lib "easyedapro") (part "W25Q32JVSSIQ"))
    )
    (comp (ref "U7")
      (value "ATGM336H-5N31")
      (footprint "easyedapro:GPSM-SMD_ATGM336H-TR")
      (description "卫星定位模块 GPS+BDS")
      (fields (field (name "Manufacturer") "杭州中科微"))
      (libsource (lib "easyedapro") (part "ATGM336H-5N31"))
    )
    (comp (ref "U8")
      (value "AT2659S")
      (footprint "easyedapro:SOT-23-6_L2.9-W1.6-P0.95-LS2.8-BR")
      (description "电源电压:1.4V~3.6V;供电电流:4.4mA;增益:20dB;P1dB:-15dBm;噪声系数:0.8dB;")
      (fields (field (name "Manufacturer") "杭州中科微"))
      (libsource (lib "easyedapro") (part "AT2659S"))
    )
    (comp (ref "C40")
      (value "10nF")
      (footprint "easyedapro:C0805")
      (description "容值:100nF;精度:±10%;额定电压:100V;材质(温度系数):X7R;")
      (fields
        (field (name "Manufacturer Part") "CC0805KKX7R0BB104")
        (field (name "Manufacturer") "YAGEO(国巨)")
      )
      (libsource (lib "easyedapro") (part "CC0805KKX7R0BB104"))
    )
    (comp (ref "C41")
      (value "15pF")
      (footprint "easyedapro:C0805")
      (description "容值:100nF;精度:±10%;额定电压:100V;材质(温度系数):X7R;")
      (fields
        (field (name "Manufacturer Part") "CC0805KKX7R0BB104")
        (field (name "Manufacturer") "YAGEO(国巨)")
      )
      (libsource (lib "easyedapro") (part "CC0805KKX7R0BB104"))
    )
    (comp (ref "C42")
      (value "220uF")
      (footprint "easyedapro:CAP-SMD_BD8.0-L8.3-W8.3-LS9.3-FD")
      (description "容值:220uF;精度:±20%;额定电压:35V;纹波电流:195mA@120Hz;等效串联电阻:-;")
      (fields
        (field (name "Manufacturer Part") "RVT220UF35V67RV0024")
        (field (name "Manufacturer") "KNSCHA(科尼盛)")
      )
      (libsource (lib "easyedapro") (part "RVT220UF35V67RV0024"))
    )
    (comp (ref "C43")
      (value "100nF")
      (footprint "easyedapro:C0805")
      (description "容值:100nF;精度:±10%;额定电压:100V;材质(温度系数):X7R;")
      (fields
        (field (name "Manufacturer Part") "CC0805KKX7R0BB104")
        (field (name "Manufacturer") "YAGEO(国巨)")
      )
      (libsource (lib "easyedapro") (part "CC0805KKX7R0BB104"))
    )
    (comp (ref "C44")
      (value "100nF")
      (footprint "easyedapro:C0805")
      (description "容值:100nF;精度:±10%;额定电压:100V;材质(温度系数):X7R;")
      (fields
        (field (name "Manufacturer Part") "CC0805KKX7R0BB104")
        (field (name "Manufacturer") "YAGEO(国巨)")
      )
      (libsource (lib "easyedapro") (part "CC0805KKX7R0BB104"))
    )
    (comp (ref "C45")
      (value "220uF")
      (footprint "easyedapro:CAP-SMD_BD8.0-L8.3-W8.3-LS9.3-FD")
      (description "容值:220uF;精度:±20%;额定电压:35V;纹波电流:195mA@120Hz;等效串联电阻:-;")
      (fields
        (field (name "Manufacturer Part") "RVT220UF35V67RV0024")
        (field (name "Manufacturer") "KNSCHA(科尼盛)")
      )
      (libsource (lib "easyedapro") (part "RVT220UF35V67RV0024"))
    )
    (comp (ref "C46")
      (value "100nF")
      (footprint "easyedapro:C0805")
      (description "容值:100nF;精度:±10%;额定电压:100V;材质(温度系数):X7R;")
      (fields
        (field (name "Manufacturer Part") "CC0805KKX7R0BB104")
        (field (name "Manufacturer") "YAGEO(国巨)")
      )
      (libsource (lib "easyedapro") (part "CC0805KKX7R0BB104"))
    )
    (comp (ref "C47")
      (value "100nF")
      (footprint "easyedapro:C0805")
      (description "容值:100nF;精度:±10%;额定电压:100V;材质(温度系数):X7R;")
      (fields
        (field (name "Manufacturer Part") "CC0805KKX7R0BB104")
        (field (name "Manufacturer") "YAGEO(国巨)")
      )
      (libsource (lib "easyedapro") (part "CC0805KKX7R0BB104"))
    )
    (comp (ref "C48")
      (value "100nF")
      (footprint "easyedapro:C0805")
      (description "容值:100nF;精度:±10%;额定电压:100V;材质(温度系数):X7R;")
      (fields
        (field (name "Manufacturer Part") "CC0805KKX7R0BB104")
        (field (name "Manufacturer") "YAGEO(国巨)")
      )
      (libsource (lib "easyedapro") (part "CC0805KKX7R0BB104"))
    )
    (comp (ref "C49")
      (value "100nF")
      (footprint "easyedapro:C0805")
      (description "容值:100nF;精度:±10%;额定电压:100V;材质(温度系数):X7R;")
      (fields
        (field (name "Manufacturer Part") "CC0805KKX7R0BB104")
        (field (name "Manufacturer") "YAGEO(国巨)")
      )
      (libsource (lib "easyedapro") (part "CC0805KKX7R0BB104"))
    )
    (comp (ref "C50")
      (value "22uF")
      (footprint "easyedapro:CASE-A_3216")
      (description "容值:22uF;精度:±10%;额定电压:10V;等效串联电阻:3Ω@100kHz;")
      (fields (field (name "Manufacturer Part") "TAJA226K010RNJ") (field (name "Manufacturer") "Kyocera AVX"))
      (libsource (lib "easyedapro") (part "TAJA226K010RNJ"))
    )
    (comp (ref "C51")
      (value "22uF")
      (footprint "easyedapro:CASE-A_3216")
      (description "容值:22uF;精度:±10%;额定电压:10V;等效串联电阻:3Ω@100kHz;")
      (fields (field (name "Manufacturer Part") "TAJA226K010RNJ") (field (name "Manufacturer") "Kyocera AVX"))
      (libsource (lib "easyedapro") (part "TAJA226K010RNJ"))
    )
    (comp (ref "C52")
      (value "100nF")
      (footprint "easyedapro:C0805")
      (description "容值:100nF;精度:±10%;额定电压:100V;材质(温度系数):X7R;")
      (fields
        (field (name "Manufacturer Part") "CC0805KKX7R0BB104")
        (field (name "Manufacturer") "YAGEO(国巨)")
      )
      (libsource (lib "easyedapro") (part "CC0805KKX7R0BB104"))
    )
    (comp (ref "C53")
      (value "10nF")
      (footprint "easyedapro:C0805")
      (description "容值:100nF;精度:±10%;额定电压:100V;材质(温度系数):X7R;")
      (fields
        (field (name "Manufacturer Part") "CC0805KKX7R0BB104")
        (field (name "Manufacturer") "YAGEO(国巨)")
      )
      (libsource (lib "easyedapro") (part "CC0805KKX7R0BB104"))
    )
    (comp (ref "C54")
      (value "10nF")
      (footprint "easyedapro:C0805")
      (description "容值:100nF;精度:±10%;额定电压:100V;材质(温度系数):X7R;")
      (fields
        (field (name "Manufacturer Part") "CC0805KKX7R0BB104")
        (field (name "Manufacturer") "YAGEO(国巨)")
      )
      (libsource (lib "easyedapro") (part "CC0805KKX7R0BB104"))
    )
    (comp (ref "CN7")
      (value "ZX-XH2.54-2PZZ")
      (footprint "easyedapro:CONN-TH_2P-P2.50_HX25003-2A")
      (fields (field (name "Manufacturer") "Megastar(兆星)"))
      (libsource (lib "easyedapro") (part "ZX-XH2.54-2PZZ"))
    )
    (comp (ref "D5")
      (value "SS34")
      (footprint "easyedapro:SMA_L4.3-W2.5-LS5.0-RD")
      (description "二极管配置:独立式;正向压降(Vf):550mV@3A;直流反向耐压(Vr):40V;平均整流电流(Io):3A;")
      (fields (field (name "Manufacturer") "TWGMC(台湾迪嘉)"))
      (libsource (lib "easyedapro") (part "SS34_C727060"))
    )
    (comp (ref "D6")
      (value "SS34")
      (footprint "easyedapro:SMA_L4.3-W2.5-LS5.0-RD")
      (description "二极管配置:独立式;正向压降(Vf):550mV@3A;直流反向耐压(Vr):40V;平均整流电流(Io):3A;")
      (fields (field (name "Manufacturer") "TWGMC(台湾迪嘉)"))
      (libsource (lib "easyedapro") (part "SS34_C727060"))
    )
    (comp (ref "D7")
      (value "SS34")
      (footprint "easyedapro:SMA_L4.3-W2.5-LS5.0-RD")
      (description "二极管配置:独立式;正向压降(Vf):550mV@3A;直流反向耐压(Vr):40V;平均整流电流(Io):3A;")
      (fields (field (name "Manufacturer") "TWGMC(台湾迪嘉)"))
      (libsource (lib "easyedapro") (part "SS34_C727060"))
    )
    (comp (ref "D8")
      (value "BZT52C3V3S")
      (footprint "easyedapro:SOD-323_L1.8-W1.3-LS2.5-RD")
      (description "二极管配置:独立式;稳压值(标称值):3.3V;稳压值(范围):3.1V~3.5V;功率:200mW;精度:-;")
      (fields (field (name "Manufacturer") "LGE(鲁光)"))
      (libsource (lib "easyedapro") (part "BZT52C3V3S_C545302"))
    )
    (comp (ref "J1") (value "~") (footprint "easyedapro:M2螺丝") (libsource (lib "easyedapro") (part "螺丝孔")))
    (comp (ref "J2") (value "~") (footprint "easyedapro:M2螺丝") (libsource (lib "easyedapro") (part "螺丝孔")))
    (comp (ref "J3") (value "~") (footprint "easyedapro:M2螺丝") (libsource (lib "easyedapro") (part "螺丝孔")))
    (comp (ref "J4") (value "~") (footprint "easyedapro:M2螺丝") (libsource (lib "easyedapro") (part "螺丝孔")))
    (comp (ref "L2")
      (value "10uH")
      (footprint "easyedapro:IND-SMD_L7.3-W6.8")
      (description "电感值:10uH;精度:±20%;额定电流:4.5A;饱和电流(Isat):5.5A;类型:一体成型电感;")
      (fields (field (name "Manufacturer Part") "FXL0630-100-M") (field (name "Manufacturer") "cjiang(长江微电)"))
      (libsource (lib "easyedapro") (part "FXL0630-100-M"))
    )
    (comp (ref "PR1")
      (value "10K")
      (footprint "easyedapro:R_3386P")
      (libsource (lib "easyedapro") (part "3386P-1-103LF"))
    )
    (comp (ref "R24") (value "ADJ") (footprint "easyedapro:R0603") (libsource (lib "easyedapro") (part "电阻")))
    (comp (ref "R25") (value "10K") (footprint "easyedapro:R0603") (libsource (lib "easyedapro") (part "电阻")))
    (comp (ref "R26") (value "ADJ") (footprint "easyedapro:R0603") (libsource (lib "easyedapro") (part "电阻")))
    (comp (ref "R27") (value "47K") (footprint "easyedapro:R0603") (libsource (lib "easyedapro") (part "电阻")))
    (comp (ref "R28") (value "27K") (footprint "easyedapro:R0603") (libsource (lib "easyedapro") (part "电阻")))
    (comp (ref "R29")
      (value "5.1K")
      (footprint "easyedapro:R0603")
      (libsource (lib "easyedapro") (part "电阻"))
    )
    (comp (ref "R30")
      (value "5.1K")
      (footprint "easyedapro:R0603")
      (libsource (lib "easyedapro") (part "电阻"))
    )
    (comp (ref "R31") (value "10K") (footprint "easyedapro:R0603") (libsource (lib "easyedapro") (part "电阻")))
    (comp (ref "R32") (value "2K") (footprint "easyedapro:R0603") (libsource (lib "easyedapro") (part "电阻")))
    (comp (ref "R33") (value "10K") (footprint "easyedapro:R0603") (libsource (lib "easyedapro") (part "电阻")))
    (comp (ref "R34") (value "2K") (footprint "easyedapro:R0603") (libsource (lib "easyedapro") (part "电阻")))
    (comp (ref "U9") (value "~") (libsource (lib "easyedapro") (part "X3DC")))
    (comp (ref "U10")
      (value "XC6206J332MR-G")
      (footprint "easyedapro:SOT-25_L3.0-W1.6-P0.95-LS2.8-BR")
      (description "输出类型:固定;最大输入电压:6V;输出电压:3.3V;最大输出电流:200mA;电源纹波抑制比(PSRR):-;输出极性:正极;")
      (fields (field (name "Manufacturer") "TOREX(特瑞仕)"))
      (libsource (lib "easyedapro") (part "XC6206J332MR-G"))
    )
    (comp (ref "U14")
      (value "GS8552-SR")
      (footprint "easyedapro:SOIC-8_L4.9-W3.9-P1.27-LS6.0-BL")
      (description "放大器数:双路;增益带宽积(GBP):1.8MHz;压摆率(SR):0.95V/us;")
      (fields (field (name "Manufacturer") "Gainsil(聚洵)"))
      (libsource (lib "easyedapro") (part "GS8552-SR"))
    )
    (comp (ref "USB1")
      (value "TYPE-C 16PIN 2MD(073)")
      (footprint "easyedapro:USB-C-SMD_TYPE-C-6PIN-2MD-073")
      (description "连接器类型:Type-C;标准:-;公母:母;端口数量:1;触点数量:16P;安装方式:卧贴;额定电流 - 电源:5A;工作温度范围:-25°C~+85°C;")
      (fields (field (name "Manufacturer") "SHOU HAN(首韩)"))
      (libsource (lib "easyedapro") (part "TYPE-C 16PIN 2MD(073)"))
    )
    (comp (ref "C55")
      (value "100nF")
      (footprint "easyedapro:C0805")
      (description "容值:100nF;精度:±10%;额定电压:100V;材质(温度系数):X7R;")
      (fields
        (field (name "Manufacturer Part") "CC0805KKX7R0BB104")
        (field (name "Manufacturer") "YAGEO(国巨)")
      )
      (libsource (lib "easyedapro") (part "CC0805KKX7R0BB104"))
    )
    (comp (ref "C56")
      (value "10nF")
      (footprint "easyedapro:C0805")
      (description "容值:100nF;精度:±10%;额定电压:100V;材质(温度系数):X7R;")
      (fields
        (field (name "Manufacturer Part") "CC0805KKX7R0BB104")
        (field (name "Manufacturer") "YAGEO(国巨)")
      )
      (libsource (lib "easyedapro") (part "CC0805KKX7R0BB104"))
    )
    (comp (ref "C57")
      (value "20pF")
      (footprint "easyedapro:C0805")
      (description "容值:100nF;精度:±10%;额定电压:100V;材质(温度系数):X7R;")
      (fields
        (field (name "Manufacturer Part") "CC0805KKX7R0BB104")
        (field (name "Manufacturer") "YAGEO(国巨)")
      )
      (libsource (lib "easyedapro") (part "CC0805KKX7R0BB104"))
    )
    (comp (ref "C58")
      (value "20pF")
      (footprint "easyedapro:C0805")
      (description "容值:100nF;精度:±10%;额定电压:100V;材质(温度系数):X7R;")
      (fields
        (field (name "Manufacturer Part") "CC0805KKX7R0BB104")
        (field (name "Manufacturer") "YAGEO(国巨)")
      )
      (libsource (lib "easyedapro") (part "CC0805KKX7R0BB104"))
    )
    (comp (ref "C59")
      (value "100nF")
      (footprint "easyedapro:C0805")
      (description "容值:100nF;精度:±10%;额定电压:100V;材质(温度系数):X7R;")
      (fields
        (field (name "Manufacturer Part") "CC0805KKX7R0BB104")
        (field (name "Manufacturer") "YAGEO(国巨)")
      )
      (libsource (lib "easyedapro") (part "CC0805KKX7R0BB104"))
    )
    (comp (ref "C60")
      (value "100nF")
      (footprint "easyedapro:C0805")
      (description "容值:100nF;精度:±10%;额定电压:100V;材质(温度系数):X7R;")
      (fields
        (field (name "Manufacturer Part") "CC0805KKX7R0BB104")
        (field (name "Manufacturer") "YAGEO(国巨)")
      )
      (libsource (lib "easyedapro") (part "CC0805KKX7R0BB104"))
    )
    (comp (ref "C61")
      (value "100nF")
      (footprint "easyedapro:C0805")
      (description "容值:100nF;精度:±10%;额定电压:100V;材质(温度系数):X7R;")
      (fields
        (field (name "Manufacturer Part") "CC0805KKX7R0BB104")
        (field (name "Manufacturer") "YAGEO(国巨)")
      )
      (libsource (lib "easyedapro") (part "CC0805KKX7R0BB104"))
    )
    (comp (ref "C62")
      (value "100nF")
      (footprint "easyedapro:C0805")
      (description "容值:100nF;精度:±10%;额定电压:100V;材质(温度系数):X7R;")
      (fields
        (field (name "Manufacturer Part") "CC0805KKX7R0BB104")
        (field (name "Manufacturer") "YAGEO(国巨)")
      )
      (libsource (lib "easyedapro") (part "CC0805KKX7R0BB104"))
    )
    (comp (ref "H2")
      (value "~")
      (footprint "easyedapro:HDR-TH_4P-P2.54-V-M")
      (libsource (lib "easyedapro") (part "PZ254V-11-04P"))
    )
    (comp (ref "LED2")
      (value "~")
      (footprint "easyedapro:LED_0805")
      (libsource (lib "easyedapro") (part "LED_G"))
    )
    (comp (ref "LED3")
      (value "~")
      (footprint "easyedapro:LED_0805")
      (libsource (lib "easyedapro") (part "LED_G"))
    )
    (comp (ref "LED4")
      (value "~")
      (footprint "easyedapro:LED_0805")
      (libsource (lib "easyedapro") (part "LED_G"))
    )
    (comp (ref "LED5")
      (value "~")
      (footprint "easyedapro:LED_0805")
      (libsource (lib "easyedapro") (part "LED_G"))
    )
    (comp (ref "PR2")
      (value "10K")
      (footprint "easyedapro:R_3386P")
      (libsource (lib "easyedapro") (part "3386P-1-103LF"))
    )
    (comp (ref "R35")
      (value "300R")
      (footprint "easyedapro:R0603")
      (libsource (lib "easyedapro") (part "电阻"))
    )
    (comp (ref "R36")
      (value "300R")
      (footprint "easyedapro:R0603")
      (libsource (lib "easyedapro") (part "电阻"))
    )
    (comp (ref "R37")
      (value "300R")
      (footprint "easyedapro:R0603")
      (libsource (lib "easyedapro") (part "电阻"))
    )
    (comp (ref "R38")
      (value "300R")
      (footprint "easyedapro:R0603")
      (libsource (lib "easyedapro") (part "电阻"))
    )
    (comp (ref "R39") (value "10K") (footprint "easyedapro:R0603") (libsource (lib "easyedapro") (part "电阻")))
    (comp (ref "R40") (value "10K") (footprint "easyedapro:R0603") (libsource (lib "easyedapro") (part "电阻")))
    (comp (ref "R41") (value "10K") (footprint "easyedapro:R0603") (libsource (lib "easyedapro") (part "电阻")))
    (comp (ref "R42") (value "0R") (footprint "easyedapro:R0603") (libsource (lib "easyedapro") (part "电阻")))
    (comp (ref "R43")
      (value "100R")
      (footprint "easyedapro:R0603")
      (libsource (lib "easyedapro") (part "电阻"))
    )
    (comp (ref "R44") (value "1M") (footprint "easyedapro:R0603") (libsource (lib "easyedapro") (part "电阻")))
    (comp (ref "R45")
      (value "100R")
      (footprint "easyedapro:R0603")
      (libsource (lib "easyedapro") (part "电阻"))
    )
    (comp (ref "U11")
      (value "GD32F307RCT6")
      (footprint "easyedapro:LQFP-64_L10.0-W10.0-P0.50-LS12.0-BL")
      (description "CPU内核:CM4;程序存储容量:256KB;RAM总容量:96KB;GPIO端口数量:51;工作电压范围:-;CPU最大主频:120MHz;程序存储器类型:FLASH;")
      (fields (field (name "Manufacturer") "GigaDevice(兆易创新)"))
      (libsource (lib "easyedapro") (part "GD32F307RCT6"))
    )
    (comp (ref "X1")
      (value "25MHz")
      (footprint "easyedapro:HC-49S_L11.4-W4.8")
      (description "晶振类型:贴片晶振;频率:25MHz;常温频差:±20ppm;外接负载电容:20pF;频率稳定度(全温):±30ppm;")
      (fields (field (name "Manufacturer Part") "X49SM25MSD2SC") (field (name "Manufacturer") "YXC(扬兴晶振)"))
      (libsource (lib "easyedapro") (part "X49SM25MSD2SC"))
    )
  )
  (nets
    (net (code "1") (name "+5V0") (class "Default")
      (node (ref "C27") (pin "2") (pinfunction "2_2") (pintype "input"))
      (node (ref "C45") (pin "1") (pinfunction "1_1") (pintype "input"))
      (node (ref "C46") (pin "2") (pinfunction "2_2") (pintype "input"))
      (node (ref "C50") (pin "1") (pinfunction "1_1") (pintype "input"))
      (node (ref "C52") (pin "1") (pinfunction "1_1") (pintype "input"))
      (node (ref "C53") (pin "1") (pinfunction "1_1") (pintype "input"))
      (node (ref "D7") (pin "1") (pinfunction "C_1") (pintype "unspecified"))
      (node (ref "L2") (pin "2") (pinfunction "2_2") (pintype "unspecified"))
      (node (ref "Q1") (pin "2") (pinfunction "S_2") (pintype "unspecified"))
      (node (ref "R26") (pin "2") (pinfunction "2_2") (pintype "input"))
      (node (ref "R9") (pin "2") (pinfunction "2_2") (pintype "input"))
      (node (ref "U10") (pin "2") (pinfunction "VIN_2") (pintype "unspecified"))
    )
    (net (code "2") (name "4G_PWR") (class "Default")
      (node (ref "R12") (pin "2") (pinfunction "2_2") (pintype "input"))
      (node (ref "U11") (pin "41") (pinfunction "PA8_41") (pintype "unspecified"))
    )
    (net (code "3") (name "4G_RXD") (class "Default")
      (node (ref "R10") (pin "1") (pinfunction "1_1") (pintype "input"))
      (node (ref "U11") (pin "42") (pinfunction "PA9_42") (pintype "unspecified"))
    )
    (net (code "4") (name "4G_TXD") (class "Default")
      (node (ref "R11") (pin "1") (pinfunction "1_1") (pintype "input"))
      (node (ref "U11") (pin "43") (pinfunction "PA10_43") (pintype "unspecified"))
    )
    (net (code "5") (name "ADC_MOT_TEMP1") (class "Default")
      (node (ref "C4") (pin "2") (pinfunction "2_2") (pintype "input"))
      (node (ref "C5") (pin "2") (pinfunction "2_2") (pintype "input"))
      (node (ref "D2") (pin "2") (pinfunction "2_2") (pintype "unspecified"))
      (node (ref "U11") (pin "8") (pinfunction "PC0_8") (pintype "unspecified"))
      (node (ref "U12") (pin "1") (pinfunction "OUT_1") (pintype "output"))
      (node (ref "U12") (pin "2") (pinfunction "INVERTING_INPUT_2") (pintype "unspecified"))
    )
    (net (code "6") (name "ADC_MOT_TEMP2") (class "Default")
      (node (ref "C11") (pin "2") (pinfunction "2_2") (pintype "input"))
      (node (ref "C12") (pin "2") (pinfunction "2_2") (pintype "input"))
      (node (ref "D4") (pin "2") (pinfunction "2_2") (pintype "unspecified"))
      (node (ref "U11") (pin "9") (pinfunction "PC1_9") (pintype "unspecified"))
      (node (ref "U12") (pin "6") (pinfunction "INVERTING_INPUT_6") (pintype "unspecified"))
      (node (ref "U12") (pin "7") (pinfunction "OUT_7") (pintype "output"))
    )
    (net (code "7") (name "ADC_MOT_TEMP3") (class "Default")
      (node (ref "C10") (pin "2") (pinfunction "2_2") (pintype "input"))
      (node (ref "C9") (pin "2") (pinfunction "2_2") (pintype "input"))
      (node (ref "D3") (pin "2") (pinfunction "2_2") (pintype "unspecified"))
      (node (ref "U11") (pin "10") (pinfunction "PC2_10") (pintype "unspecified"))
      (node (ref "U13") (pin "6") (pinfunction "INVERTING_INPUT_6") (pintype "unspecified"))
      (node (ref "U13") (pin "7") (pinfunction "OUT_7") (pintype "output"))
    )
    (net (code "8") (name "ADC_MOT_TEMP4") (class "Default")
      (node (ref "C3") (pin "2") (pinfunction "2_2") (pintype "input"))
      (node (ref "C7") (pin "2") (pinfunction "2_2") (pintype "input"))
      (node (ref "D1") (pin "2") (pinfunction "2_2") (pintype "unspecified"))
      (node (ref "U11") (pin "11") (pinfunction "PC3_11") (pintype "unspecified"))
      (node (ref "U13") (pin "1") (pinfunction "OUT_1") (pintype "output"))
      (node (ref "U13") (pin "2") (pinfunction "INVERTING_INPUT_2") (pintype "unspecified"))
    )
    (net (code "9") (name "BAT_ADC") (class "Default")
      (node (ref "U11") (pin "24") (pinfunction "PC4_24") (pintype "unspecified"))
      (node (ref "U14") (pin "6") (pinfunction "INVERTING_INPUT_6") (pintype "unspecified"))
      (node (ref "U14") (pin "7") (pinfunction "OUT_7") (pintype "output"))
    )
    (net (code "10") (name "BAT_INT") (class "Default")
      (node (ref "U11") (pin "50") (pinfunction "PA15_50") (pintype "unspecified"))
      (node (ref "U14") (pin "1") (pinfunction "OUT_1") (pintype "output"))
      (node (ref "U14") (pin "2") (pinfunction "INVERTING_INPUT_2") (pintype "unspecified"))
    )
    (net (code "11") (name "GND") (class "Default")
      (node (ref "BT1") (pin "2") (pinfunction "2_2") (pintype "input"))
      (node (ref "C1") (pin "1") (pinfunction "1_1") (pintype "input"))
      (node (ref "C10") (pin "1") (pinfunction "1_1") (pintype "input"))
      (node (ref "C11") (pin "1") (pinfunction "1_1") (pintype "input"))
      (node (ref "C12") (pin "1") (pinfunction "1_1") (pintype "input"))
      (node (ref "C13") (pin "1") (pinfunction "1_1") (pintype "input"))
      (node (ref "C14") (pin "1") (pinfunction "1_1") (pintype "input"))
      (node (ref "C15") (pin "1") (pinfunction "1_1") (pintype "input"))
      (node (ref "C16") (pin "2") (pinfunction "2_2") (pintype "input"))
      (node (ref "C17") (pin "1") (pinfunction "1_1") (pintype "input"))
      (node (ref "C18") (pin "1") (pinfunction "1_1") (pintype "input"))
      (node (ref "C19") (pin "2") (pinfunction "2_2") (pintype "input"))
      (node (ref "C2") (pin "1") (pinfunction "1_1") (pintype "input"))
      (node (ref "C20") (pin "1") (pinfunction "1_1") (pintype "input"))
      (node (ref "C21") (pin "1") (pinfunction "1_1") (pintype "input"))
      (node (ref "C22") (pin "2") (pinfunction "2_2") (pintype "input"))
      (node (ref "C23") (pin "1") (pinfunction "1_1") (pintype "input"))
      (node (ref "C24") (pin "1") (pinfunction "1_1") (pintype "input"))
      (node (ref "C25") (pin "2") (pinfunction "2_2") (pintype "input"))
      (node (ref "C26") (pin "1") (pinfunction "1_1") (pintype "input"))
      (node (ref "C28") (pin "2") (pinfunction "2_2") (pintype "input"))
      (node (ref "C29") (pin "2") (pinfunction "2_2") (pintype "input"))
      (node (ref "C3") (pin "1") (pinfunction "1_1") (pintype "input"))
      (node (ref "C30") (pin "2") (pinfunction "2_2") (pintype "input"))
      (node (ref "C31") (pin "1") (pinfunction "1_1") (pintype "input"))
      (node (ref "C32") (pin "2") (pinfunction "2_2") (pintype "input"))
      (node (ref "C33") (pin "1") (pinfunction "1_1") (pintype "input"))
      (node (ref "C34") (pin "2") (pinfunction "2_2") (pintype "input"))
      (node (ref "C35") (pin "1") (pinfunction "1_1") (pintype "input"))
      (node (ref "C36") (pin "2") (pinfunction "2_2") (pintype "input"))
      (node (ref "C38") (pin "1") (pinfunction "1_1") (pintype "input"))
      (node (ref "C39") (pin "1") (pinfunction "1_1") (pintype "input"))
      (node (ref "C4") (pin "1") (pinfunction "1_1") (pintype "input"))
      (node (ref "C40") (pin "2") (pinfunction "2_2") (pintype "input"))
      (node (ref "C41") (pin "1") (pinfunction "1_1") (pintype "input"))
      (node (ref "C42") (pin "2") (pinfunction "2_2") (pintype "input"))
      (node (ref "C43") (pin "2") (pinfunction "2_2") (pintype "input"))
      (node (ref "C45") (pin "2") (pinfunction "2_2") (pintype "input"))
      (node (ref "C46") (pin "1") (pinfunction "1_1") (pintype "input"))
      (node (ref "C47") (pin "2") (pinfunction "2_2") (pintype "input"))
      (node (ref "C48") (pin "2") (pinfunction "2_2") (pintype "input"))
      (node (ref "C49") (pin "2") (pinfunction "2_2") (pintype "input"))
      (node (ref "C5") (pin "1") (pinfunction "1_1") (pintype "input"))
      (node (ref "C50") (pin "2") (pinfunction "2_2") (pintype "input"))
      (node (ref "C51") (pin "2") (pinfunction "2_2") (pintype "input"))
      (node (ref "C52") (pin "2") (pinfunction "2_2") (pintype "input"))
      (node (ref "C53") (pin "2") (pinfunction "2_2") (pintype "input"))
      (node (ref "C54") (pin "2") (pinfunction "2_2") (pintype "input"))
      (node (ref "C55") (pin "2") (pinfunction "2_2") (pintype "input"))
      (node (ref "C56") (pin "1") (pinfunction "1_1") (pintype "input"))
      (node (ref "C57") (pin "1") (pinfunction "1_1") (pintype "input"))
      (node (ref "C58") (pin "1") (pinfunction "1_1") (pintype "input"))
      (node (ref "C59") (pin "2") (pinfunction "2_2") (pintype "input"))
      (node (ref "C6") (pin "1") (pinfunction "1_1") (pintype "input"))
      (node (ref "C60") (pin "2") (pinfunction "2_2") (pintype "input"))
      (node (ref "C61") (pin "2") (pinfunction "2_2") (pintype "input"))
      (node (ref "C62") (pin "2") (pinfunction "2_2") (pintype "input"))
      (node (ref "C7") (pin "1") (pinfunction "1_1") (pintype "input"))
      (node (ref "C8") (pin "1") (pinfunction "1_1") (pintype "input"))
      (node (ref "C9") (pin "1") (pinfunction "1_1") (pintype "input"))
      (node (ref "CN1") (pin "2") (pinfunction "2_2") (pintype "unspecified"))
      (node (ref "CN2") (pin "2") (pinfunction "2_2") (pintype "unspecified"))
      (node (ref "CN3") (pin "2") (pinfunction "2_2") (pintype "unspecified"))
      (node (ref "CN4") (pin "2") (pinfunction "2_2") (pintype "unspecified"))
      (node (ref "CN5") (pin "1") (pinfunction "1_1") (pintype "unspecified"))
      (node (ref "CN5") (pin "6") (pinfunction "6_6") (pintype "unspecified"))
      (node (ref "CN5") (pin "7") (pinfunction "7_7") (pintype "unspecified"))
      (node (ref "CN6") (pin "10") (pinfunction "10_10") (pintype "unspecified"))
      (node (ref "CN6") (pin "8") (pinfunction "8_8") (pintype "unspecified"))
      (node (ref "CN6") (pin "9") (pinfunction "9_9") (pintype "unspecified"))
      (node (ref "CN7") (pin "2") (pinfunction "2_2") (pintype "unspecified"))
      (node (ref "D1") (pin "1") (pinfunction "1_1") (pintype "unspecified"))
      (node (ref "D2") (pin "1") (pinfunction "1_1") (pintype "unspecified"))
      (node (ref "D3") (pin "1") (pinfunction "1_1") (pintype "unspecified"))
      (node (ref "D4") (pin "1") (pinfunction "1_1") (pintype "unspecified"))
      (node (ref "D6") (pin "2") (pinfunction "A_2") (pintype "unspecified"))
      (node (ref "D8") (pin "2") (pinfunction "A_2") (pintype "unspecified"))
      (node (ref "H1") (pin "4") (pinfunction "4_4") (pintype "unspecified"))
      (node (ref "H2") (pin "3") (pinfunction "3_3") (pintype "unspecified"))
      (node (ref "J1") (pin "1") (pinfunction "1_1") (pintype "input"))
      (node (ref "J2") (pin "1") (pinfunction "1_1") (pintype "input"))
      (node (ref "J3") (pin "1") (pinfunction "1_1") (pintype "input"))
      (node (ref "J4") (pin "1") (pinfunction "1_1") (pintype "input"))
      (node (ref "PR1") (pin "3") (pinfunction "3_3") (pintype "input"))
      (node (ref "PR2") (pin "1") (pinfunction "1_1") (pintype "input"))
      (node (ref "Q2") (pin "2") (pinfunction "E_2") (pintype "unspecified"))
      (node (ref "R1") (pin "1") (pinfunction "1_1") (pintype "input"))
      (node (ref "R13") (pin "1") (pinfunction "1_1") (pintype "input"))
      (node (ref "R19") (pin "1") (pinfunction "1_1") (pintype "input"))
      (node (ref "R2") (pin "1") (pinfunction "1_1") (pintype "input"))
      (node (ref "R24") (pin "1") (pinfunction "1_1") (pintype "input"))
      (node (ref "R27") (pin "2") (pinfunction "2_2") (pintype "input"))
      (node (ref "R29") (pin "2") (pinfunction "2_2") (pintype "input"))
      (node (ref "R3") (pin "1") (pinfunction "1_1") (pintype "input"))
      (node (ref "R30") (pin "2") (pinfunction "2_2") (pintype "input"))
      (node (ref "R32") (pin "1") (pinfunction "1_1") (pintype "input"))
      (node (ref "R34") (pin "2") (pinfunction "2_2") (pintype "input"))
      (node (ref "R39") (pin "1") (pinfunction "1_1") (pintype "input"))
      (node (ref "R4") (pin "1") (pinfunction "1_1") (pintype "input"))
      (node (ref "R5") (pin "2") (pinfunction "2_2") (pintype "input"))
      (node (ref "R6") (pin "2") (pinfunction "2_2") (pintype "input"))
      (node (ref "R7") (pin "2") (pinfunction "2_2") (pintype "input"))
      (node (ref "R8") (pin "2") (pinfunction "2_2") (pintype "input"))
      (node (ref "RF1") (pin "1") (pinfunction "1_1") (pintype "unspecified"))
      (node (ref "RF1") (pin "2") (pinfunction "2_2") (pintype "unspecified"))
      (node (ref "RF1") (pin "3") (pinfunction "3_3") (pintype "unspecified"))
      (node (ref "RF1") (pin "4") (pinfunction "4_4") (pintype "unspecified"))
      (node (ref "U1") (pin "1") (pinfunction "GND_1") (pintype "unspecified"))
      (node (ref "U1") (pin "9") (pinfunction "EP_9") (pintype "unspecified"))
      (node (ref "U10") (pin "4") (pinfunction "VSS_4") (pintype "unspecified"))
      (node (ref "U11") (pin "12") (pinfunction "VSSA_12") (pintype "unspecified"))
      (node (ref "U11") (pin "18") (pinfunction "VSS_4_18") (pintype "unspecified"))
      (node (ref "U11") (pin "31") (pinfunction "VSS_1_31") (pintype "unspecified"))
      (node (ref "U11") (pin "47") (pinfunction "VSS_2_47") (pintype "unspecified"))
      (node (ref "U11") (pin "63") (pinfunction "VSS_3_63") (pintype "unspecified"))
      (node (ref "U12") (pin "4") (pinfunction "-V_4") (pintype "unspecified"))
      (node (ref "U13") (pin "4") (pinfunction "-V_4") (pintype "unspecified"))
      (node (ref "U14") (pin "4") (pinfunction "-V_4") (pintype "unspecified"))
      (node (ref "U2") (pin "1") (pinfunction "GND_1") (pintype "unspecified"))
      (node (ref "U2") (pin "9") (pinfunction "EP_9") (pintype "unspecified"))
      (node (ref "U3") (pin "1") (pinfunction "GND_1") (pintype "unspecified"))
      (node (ref "U3") (pin "9") (pinfunction "EP_9") (pintype "unspecified"))
      (node (ref "U4") (pin "1") (pinfunction "GND_1") (pintype "unspecified"))
      (node (ref "U4") (pin "9") (pinfunction "EP_9") (pintype "unspecified"))
      (node (ref "U5") (pin "1") (pinfunction "CLKIN_1") (pintype "unspecified"))
      (node (ref "U5") (pin "11") (pinfunction "FSYNC_11") (pintype "unspecified"))
      (node (ref "U5") (pin "18") (pinfunction "GND_18") (pintype "unspecified"))
      (node (ref "U6") (pin "4") (pinfunction "GND_4") (pintype "unspecified"))
      (node (ref "U7") (pin "1") (pinfunction "GND_1") (pintype "unspecified"))
      (node (ref "U7") (pin "10") (pinfunction "GND_10") (pintype "unspecified"))
      (node (ref "U7") (pin "12") (pinfunction "GND_12") (pintype "unspecified"))
      (node (ref "U8") (pin "2") (pinfunction "GND_2") (pintype "unspecified"))
      (node (ref "U8") (pin "3") (pinfunction "GND_3") (pintype "unspecified"))
      (node (ref "U9") (pin "7") (pinfunction "GND_7") (pintype "input"))
      (node (ref "U9") (pin "9") (pinfunction "PAD_9") (pintype "input"))
      (node (ref "USB1") (pin "1") (pinfunction "GND_1") (pintype "unspecified"))
      (node (ref "USB1") (pin "12") (pinfunction "GND_12") (pintype "unspecified"))
      (node (ref "USB1") (pin "13") (pinfunction "SHELL_13") (pintype "unspecified"))
      (node (ref "USB1") (pin "14") (pinfunction "SHELL_14") (pintype "unspecified"))
    )
    (net (code "12") (name "GPS_PWR") (class "Default")
      (node (ref "U11") (pin "27") (pinfunction "PB1_27") (pintype "unspecified"))
      (node (ref "U7") (pin "5") (pinfunction "ON/OFF_5") (pintype "unspecified"))
    )
    (net (code "13") (name "GPS_RST") (class "Default")
      (node (ref "U11") (pin "26") (pinfunction "PB0_26") (pintype "unspecified"))
      (node (ref "U7") (pin "9") (pinfunction "NRESET_9") (pintype "unspecified"))
    )
    (net (code "14") (name "GPS_RXD") (class "Default")
      (node (ref "R22") (pin "1") (pinfunction "1_1") (pintype "input"))
      (node (ref "U11") (pin "29") (pinfunction "PB10_29") (pintype "unspecified"))
    )
    (net (code "15") (name "GPS_TXD") (class "Default")
      (node (ref "R21") (pin "1") (pinfunction "1_1") (pintype "input"))
      (node (ref "U11") (pin "30") (pinfunction "PB11_30") (pintype "unspecified"))
    )
    (net (code "16") (name "MM_CS") (class "Default")
      (node (ref "R20") (pin "1") (pinfunction "1_1") (pintype "input"))
      (node (ref "U11") (pin "39") (pinfunction "PC8_39") (pintype "unspecified"))
      (node (ref "U6") (pin "1") (pinfunction "CS#_1") (pintype "unspecified"))
    )
    (net (code "17") (name "Net-(C37-Pad1)") (class "Default")
      (node (ref "C37") (pin "1") (pinfunction "1_1") (pintype "input"))
      (node (ref "RF1") (pin "5") (pinfunction "5_5") (pintype "unspecified"))
    )
    (net (code "18") (name "Net-(C37-Pad2)") (class "Default")
      (node (ref "C37") (pin "2") (pinfunction "2_2") (pintype "input"))
      (node (ref "L1") (pin "2") (pinfunction "2_2") (pintype "input"))
    )
    (net (code "19") (name "Net-(C40-Pad1)") (class "Default")
      (node (ref "C40") (pin "1") (pinfunction "1_1") (pintype "input"))
      (node (ref "R28") (pin "2") (pinfunction "2_2") (pintype "input"))
    )
    (net (code "20") (name "Net-(CN5-Pad4)") (class "Default")
      (node (ref "CN5") (pin "4") (pinfunction "4_4") (pintype "unspecified"))
      (node (ref "R11") (pin "2") (pinfunction "2_2") (pintype "input"))
    )
    (net (code "21") (name "Net-(CN5-Pad5)") (class "Default")
      (node (ref "CN5") (pin "5") (pinfunction "5_5") (pintype "unspecified"))
      (node (ref "R10") (pin "2") (pinfunction "2_2") (pintype "input"))
    )
    (net (code "22") (name "Net-(D5-C)") (class "Default")
      (node (ref "C42") (pin "1") (pinfunction "1_1") (pintype "input"))
      (node (ref "C43") (pin "1") (pinfunction "1_1") (pintype "input"))
      (node (ref "D5") (pin "1") (pinfunction "C_1") (pintype "unspecified"))
      (node (ref "U9") (pin "2") (pinfunction "VIN_2") (pintype "input"))
      (node (ref "U9") (pin "3") (pinfunction "EN_3") (pintype "input"))
    )
    (net (code "23") (name "Net-(D6-C)") (class "Default")
      (node (ref "C44") (pin "1") (pinfunction "1_1") (pintype "input"))
      (node (ref "D6") (pin "1") (pinfunction "C_1") (pintype "unspecified"))
      (node (ref "L2") (pin "1") (pinfunction "1_1") (pintype "unspecified"))
      (node (ref "U9") (pin "8") (pinfunction "SW_8") (pintype "input"))
    )
    (net (code "24") (name "Net-(D8-C)") (class "Default")
      (node (ref "C48") (pin "1") (pinfunction "1_1") (pintype "input"))
      (node (ref "D8") (pin "1") (pinfunction "C_1") (pintype "unspecified"))
      (node (ref "R31") (pin "2") (pinfunction "2_2") (pintype "input"))
      (node (ref "R32") (pin "2") (pinfunction "2_2") (pintype "input"))
      (node (ref "U14") (pin "5") (pinfunction "NONINVERTING_INPUT_5") (pintype "unspecified"))
    )
    (net (code "25") (name "Net-(H2-Pad1)") (class "Default")
      (node (ref "H2") (pin "1") (pinfunction "1_1") (pintype "unspecified"))
      (node (ref "R43") (pin "1") (pinfunction "1_1") (pintype "input"))
    )
    (net (code "26") (name "Net-(H2-Pad4)") (class "Default")
      (node (ref "H2") (pin "4") (pinfunction "4_4") (pintype "unspecified"))
      (node (ref "R45") (pin "1") (pinfunction "1_1") (pintype "input"))
    )
    (net (code "27") (name "Net-(LED1-C)") (class "Default")
      (node (ref "LED1") (pin "1") (pinfunction "C_1") (pintype "input"))
      (node (ref "R23") (pin "1") (pinfunction "1_1") (pintype "input"))
    )
    (net (code "28") (name "Net-(LED2-A)") (class "Default")
      (node (ref "LED2") (pin "2") (pinfunction "A_2") (pintype "input"))
      (node (ref "R35") (pin "1") (pinfunction "1_1") (pintype "input"))
    )
    (net (code "29") (name "Net-(LED3-A)") (class "Default")
      (node (ref "LED3") (pin "2") (pinfunction "A_2") (pintype "input"))
      (node (ref "R36") (pin "1") (pinfunction "1_1") (pintype "input"))
    )
    (net (code "30") (name "Net-(LED4-A)") (class "Default")
      (node (ref "LED4") (pin "2") (pinfunction "A_2") (pintype "input"))
      (node (ref "R37") (pin "1") (pinfunction "1_1") (pintype "input"))
    )
    (net (code "31") (name "Net-(LED5-A)") (class "Default")
      (node (ref "LED5") (pin "2") (pinfunction "A_2") (pintype "input"))
      (node (ref "R38") (pin "1") (pinfunction "1_1") (pintype "input"))
    )
    (net (code "32") (name "Net-(PR2-Pad2)") (class "Default")
      (node (ref "PR2") (pin "2") (pinfunction "2_2") (pintype "input"))
      (node (ref "R41") (pin "1") (pinfunction "1_1") (pintype "input"))
    )
    (net (code "33") (name "Net-(Q1-D)") (class "Default")
      (node (ref "CN5") (pin "2") (pinfunction "2_2") (pintype "unspecified"))
      (node (ref "CN5") (pin "3") (pinfunction "3_3") (pintype "unspecified"))
      (node (ref "Q1") (pin "3") (pinfunction "D_3") (pintype "unspecified"))
    )
    (net (code "34") (name "Net-(Q1-G)") (class "Default")
      (node (ref "C27") (pin "1") (pinfunction "1_1") (pintype "input"))
      (node (ref "Q1") (pin "1") (pinfunction "G_1") (pintype "unspecified"))
      (node (ref "Q2") (pin "3") (pinfunction "C_3") (pintype "unspecified"))
      (node (ref "R9") (pin "1") (pinfunction "1_1") (pintype "input"))
    )
    (net (code "35") (name "Net-(Q2-B)") (class "Default")
      (node (ref "Q2") (pin "1") (pinfunction "B_1") (pintype "unspecified"))
      (node (ref "R12") (pin "1") (pinfunction "1_1") (pintype "input"))
      (node (ref "R13") (pin "2") (pinfunction "2_2") (pintype "input"))
    )
    (net (code "36") (name "Net-(R24-Pad2)") (class "Default")
      (node (ref "R24") (pin "2") (pinfunction "2_2") (pintype "input"))
      (node (ref "R25") (pin "1") (pinfunction "1_1") (pintype "input"))
    )
    (net (code "37") (name "Net-(U1-OUT1)") (class "Default")
      (node (ref "CN4") (pin "3") (pinfunction "3_3") (pintype "unspecified"))
      (node (ref "U1") (pin "6") (pinfunction "OUT1_6") (pintype "unspecified"))
    )
    (net (code "38") (name "Net-(U1-OUT2)") (class "Default")
      (node (ref "CN4") (pin "1") (pinfunction "1_1") (pintype "unspecified"))
      (node (ref "U1") (pin "8") (pinfunction "OUT2_8") (pintype "unspecified"))
    )
    (net (code "39") (name "Net-(U1-RS)") (class "Default")
      (node (ref "R5") (pin "1") (pinfunction "1_1") (pintype "input"))
      (node (ref "U1") (pin "7") (pinfunction "RS_7") (pintype "unspecified"))
    )
    (net (code "40") (name "Net-(U2-OUT1)") (class "Default")
      (node (ref "CN1") (pin "3") (pinfunction "3_3") (pintype "unspecified"))
      (node (ref "U2") (pin "6") (pinfunction "OUT1_6") (pintype "unspecified"))
    )
    (net (code "41") (name "Net-(U2-OUT2)") (class "Default")
      (node (ref "CN1") (pin "1") (pinfunction "1_1") (pintype "unspecified"))
      (node (ref "U2") (pin "8") (pinfunction "OUT2_8") (pintype "unspecified"))
    )
    (net (code "42") (name "Net-(U2-RS)") (class "Default")
      (node (ref "R6") (pin "1") (pinfunction "1_1") (pintype "input"))
      (node (ref "U2") (pin "7") (pinfunction "RS_7") (pintype "unspecified"))
    )
    (net (code "43") (name "Net-(U3-OUT1)") (class "Default")
      (node (ref "CN3") (pin "3") (pinfunction "3_3") (pintype "unspecified"))
      (node (ref "U3") (pin "6") (pinfunction "OUT1_6") (pintype "unspecified"))
    )
    (net (code "44") (name "Net-(U3-OUT2)") (class "Default")
      (node (ref "CN3") (pin "1") (pinfunction "1_1") (pintype "unspecified"))
      (node (ref "U3") (pin "8") (pinfunction "OUT2_8") (pintype "unspecified"))
    )
    (net (code "45") (name "Net-(U3-RS)") (class "Default")
      (node (ref "R7") (pin "1") (pinfunction "1_1") (pintype "input"))
      (node (ref "U3") (pin "7") (pinfunction "RS_7") (pintype "unspecified"))
    )
    (net (code "46") (name "Net-(U4-OUT1)") (class "Default")
      (node (ref "CN2") (pin "3") (pinfunction "3_3") (pintype "unspecified"))
      (node (ref "U4") (pin "6") (pinfunction "OUT1_6") (pintype "unspecified"))
    )
    (net (code "47") (name "Net-(U4-OUT2)") (class "Default")
      (node (ref "CN2") (pin "1") (pinfunction "1_1") (pintype "unspecified"))
      (node (ref "U4") (pin "8") (pinfunction "OUT2_8") (pintype "unspecified"))
    )
    (net (code "48") (name "Net-(U4-RS)") (class "Default")
      (node (ref "R8") (pin "1") (pinfunction "1_1") (pintype "input"))
      (node (ref "U4") (pin "7") (pinfunction "RS_7") (pintype "unspecified"))
    )
    (net (code "49") (name "Net-(U5-AD0)") (class "Default")
      (node (ref "R19") (pin "2") (pinfunction "2_2") (pintype "input"))
      (node (ref "U5") (pin "9") (pinfunction "AD0_9") (pintype "unspecified"))
    )
    (net (code "50") (name "Net-(U5-AUX_CL)") (class "Default")
      (node (ref "H1") (pin "2") (pinfunction "2_2") (pintype "unspecified"))
      (node (ref "U5") (pin "7") (pinfunction "AUX_CL_7") (pintype "unspecified"))
    )
    (net (code "51") (name "Net-(U5-AUX_DA)") (class "Default")
      (node (ref "H1") (pin "3") (pinfunction "3_3") (pintype "unspecified"))
      (node (ref "U5") (pin "6") (pinfunction "AUX_DA_6") (pintype "unspecified"))
    )
    (net (code "52") (name "Net-(U5-CPOUT)") (class "Default")
      (node (ref "C31") (pin "2") (pinfunction "2_2") (pintype "input"))
      (node (ref "U5") (pin "20") (pinfunction "CPOUT_20") (pintype "unspecified"))
    )
    (net (code "53") (name "Net-(U5-REGOUT)") (class "Default")
      (node (ref "C32") (pin "1") (pinfunction "1_1") (pintype "input"))
      (node (ref "U5") (pin "10") (pinfunction "REGOUT_10") (pintype "unspecified"))
    )
    (net (code "54") (name "Net-(U7-1PPS)") (class "Default")
      (node (ref "R23") (pin "2") (pinfunction "2_2") (pintype "input"))
      (node (ref "U7") (pin "4") (pinfunction "1PPS_4") (pintype "unspecified"))
    )
    (net (code "55") (name "Net-(U7-RF_IN)") (class "Default")
      (node (ref "U7") (pin "11") (pinfunction "RF_IN_11") (pintype "unspecified"))
      (node (ref "U8") (pin "4") (pinfunction "RFOUT_4") (pintype "unspecified"))
    )
    (net (code "56") (name "Net-(U7-RXD)") (class "Default")
      (node (ref "R22") (pin "2") (pinfunction "2_2") (pintype "input"))
      (node (ref "U7") (pin "3") (pinfunction "RXD_3") (pintype "unspecified"))
    )
    (net (code "57") (name "Net-(U7-TXD)") (class "Default")
      (node (ref "R21") (pin "2") (pinfunction "2_2") (pintype "input"))
      (node (ref "U7") (pin "2") (pinfunction "TXD_2") (pintype "unspecified"))
    )
    (net (code "58") (name "Net-(U7-VBAT)") (class "Default")
      (node (ref "BT1") (pin "1") (pinfunction "1_1") (pintype "input"))
      (node (ref "U7") (pin "6") (pinfunction "VBAT_6") (pintype "unspecified"))
    )
    (net (code "59") (name "Net-(U7-VCC_RF)") (class "Default")
      (node (ref "C35") (pin "2") (pinfunction "2_2") (pintype "input"))
      (node (ref "U7") (pin "14") (pinfunction "VCC_RF_14") (pintype "unspecified"))
    )
    (net (code "60") (name "Net-(U8-RFIN)") (class "Default")
      (node (ref "L1") (pin "1") (pinfunction "1_1") (pintype "input"))
      (node (ref "U8") (pin "1") (pinfunction "RFIN_1") (pintype "unspecified"))
    )
    (net (code "61") (name "Net-(U9-BOOT)") (class "Default")
      (node (ref "C44") (pin "2") (pinfunction "2_2") (pintype "input"))
      (node (ref "U9") (pin "1") (pinfunction "BOOT_1") (pintype "input"))
    )
    (net (code "62") (name "Net-(U9-CMP)") (class "Default")
      (node (ref "C41") (pin "2") (pinfunction "2_2") (pintype "input"))
      (node (ref "R28") (pin "1") (pinfunction "1_1") (pintype "input"))
      (node (ref "U9") (pin "6") (pinfunction "CMP_6") (pintype "input"))
    )
    (net (code "63") (name "Net-(U9-FB)") (class "Default")
      (node (ref "R25") (pin "2") (pinfunction "2_2") (pintype "input"))
      (node (ref "R26") (pin "1") (pinfunction "1_1") (pintype "input"))
      (node (ref "U9") (pin "5") (pinfunction "FB_5") (pintype "input"))
    )
    (net (code "64") (name "Net-(U9-RT)") (class "Default")
      (node (ref "R27") (pin "1") (pinfunction "1_1") (pintype "input"))
      (node (ref "U9") (pin "4") (pinfunction "RT_4") (pintype "input"))
    )
    (net (code "65") (name "Net-(U11-BOOT0)") (class "Default")
      (node (ref "R39") (pin "2") (pinfunction "2_2") (pintype "input"))
      (node (ref "U11") (pin "60") (pinfunction "BOOT0_60") (pintype "unspecified"))
    )
    (net (code "66") (name "Net-(U11-NRST)") (class "Default")
      (node (ref "C55") (pin "1") (pinfunction "1_1") (pintype "input"))
      (node (ref "R40") (pin "1") (pinfunction "1_1") (pintype "input"))
      (node (ref "U11") (pin "7") (pinfunction "NRST_7") (pintype "unspecified"))
    )
    (net (code "67") (name "Net-(U11-PA13)") (class "Default")
      (node (ref "R45") (pin "2") (pinfunction "2_2") (pintype "input"))
      (node (ref "U11") (pin "46") (pinfunction "PA13_46") (pintype "unspecified"))
    )
    (net (code "68") (name "Net-(U11-PA14)") (class "Default")
      (node (ref "R43") (pin "2") (pinfunction "2_2") (pintype "input"))
      (node (ref "U11") (pin "49") (pinfunction "PA14_49") (pintype "unspecified"))
    )
    (net (code "69") (name "Net-(U11-VDDA)") (class "Default")
      (node (ref "R42") (pin "1") (pinfunction "1_1") (pintype "input"))
      (node (ref "U11") (pin "13") (pinfunction "VDDA_13") (pintype "unspecified"))
    )
    (net (code "70") (name "Net-(U12A-NONINVERTING_INPUT)") (class "Default")
      (node (ref "C8") (pin "2") (pinfunction "2_2") (pintype "input"))
      (node (ref "R2") (pin "2") (pinfunction "2_2") (pintype "input"))
      (node (ref "RT1") (pin "2") (pinfunction "2_2") (pintype "input"))
      (node (ref "U12") (pin "3") (pinfunction "NONINVERTING_INPUT_3") (pintype "unspecified"))
    )
    (net (code "71") (name "Net-(U12B-NONINVERTING_INPUT)") (class "Default")
      (node (ref "C14") (pin "2") (pinfunction "2_2") (pintype "input"))
      (node (ref "R4") (pin "2") (pinfunction "2_2") (pintype "input"))
      (node (ref "RT2") (pin "2") (pinfunction "2_2") (pintype "input"))
      (node (ref "U12") (pin "5") (pinfunction "NONINVERTING_INPUT_5") (pintype "unspecified"))
    )
    (net (code "72") (name "Net-(U13A-NONINVERTING_INPUT)") (class "Default")
      (node (ref "C6") (pin "2") (pinfunction "2_2") (pintype "input"))
      (node (ref "R1") (pin "2") (pinfunction "2_2") (pintype "input"))
      (node (ref "RT4") (pin "2") (pinfunction "2_2") (pintype "input"))
      (node (ref "U13") (pin "3") (pinfunction "NONINVERTING_INPUT_3") (pintype "unspecified"))
    )
    (net (code "73") (name "Net-(U13B-NONINVERTING_INPUT)") (class "Default")
      (node (ref "C13") (pin "2") (pinfunction "2_2") (pintype "input"))
      (node (ref "R3") (pin "2") (pinfunction "2_2") (pintype "input"))
      (node (ref "RT3") (pin "2") (pinfunction "2_2") (pintype "input"))
      (node (ref "U13") (pin "5") (pinfunction "NONINVERTING_INPUT_5") (pintype "unspecified"))
    )
    (net (code "74") (name "Net-(U14A-NONINVERTING_INPUT)") (class "Default")
      (node (ref "PR1") (pin "1") (pinfunction "1_1") (pintype "input"))
      (node (ref "R33") (pin "1") (pinfunction "1_1") (pintype "input"))
      (node (ref "R34") (pin "1") (pinfunction "1_1") (pintype "input"))
      (node (ref "U14") (pin "3") (pinfunction "NONINVERTING_INPUT_3") (pintype "unspecified"))
    )
    (net (code "75") (name "Net-(USB1-CC1)") (class "Default")
      (node (ref "R30") (pin "1") (pinfunction "1_1") (pintype "input"))
      (node (ref "USB1") (pin "4") (pinfunction "CC1_4") (pintype "unspecified"))
    )
    (net (code "76") (name "Net-(USB1-CC2)") (class "Default")
      (node (ref "R29") (pin "1") (pinfunction "1_1") (pintype "input"))
      (node (ref "USB1") (pin "10") (pinfunction "CC2_10") (pintype "unspecified"))
    )
    (net (code "77") (name "OSC_IN") (class "Default")
      (node (ref "C57") (pin "2") (pinfunction "2_2") (pintype "input"))
      (node (ref "R44") (pin "1") (pinfunction "1_1") (pintype "input"))
      (node (ref "U11") (pin "5") (pinfunction "PD0-OSC_IN_5") (pintype "unspecified"))
      (node (ref "X1") (pin "2") (pinfunction "OSC2_2") (pintype "input"))
    )
    (net (code "78") (name "OSC_OUT") (class "Default")
      (node (ref "C58") (pin "2") (pinfunction "2_2") (pintype "input"))
      (node (ref "R44") (pin "2") (pinfunction "2_2") (pintype "input"))
      (node (ref "U11") (pin "6") (pinfunction "PD1-OSC_OUT_6") (pintype "unspecified"))
      (node (ref "X1") (pin "1") (pinfunction "OSC1_1") (pintype "input"))
    )
    (net (code "79") (name "RF_CE") (class "Default")
      (node (ref "CN6") (pin "2") (pinfunction "2_2") (pintype "unspecified"))
      (node (ref "R14") (pin "1") (pinfunction "1_1") (pintype "input"))
      (node (ref "U11") (pin "37") (pinfunction "PC6_37") (pintype "unspecified"))
    )
    (net (code "80") (name "RF_CS") (class "Default")
      (node (ref "CN6") (pin "3") (pinfunction "3_3") (pintype "unspecified"))
      (node (ref "R15") (pin "1") (pinfunction "1_1") (pintype "input"))
      (node (ref "U11") (pin "33") (pinfunction "PB12_33") (pintype "unspecified"))
    )
    (net (code "81") (name "RF_IRQ") (class "Default")
      (node (ref "CN6") (pin "7") (pinfunction "7_7") (pintype "unspecified"))
      (node (ref "R16") (pin "1") (pinfunction "1_1") (pintype "input"))
      (node (ref "U11") (pin "38") (pinfunction "PC7_38") (pintype "unspecified"))
    )
    (net (code "82") (name "RF_MISO") (class "Default")
      (node (ref "CN6") (pin "6") (pinfunction "6_6") (pintype "unspecified"))
      (node (ref "U11") (pin "35") (pinfunction "PB14_35") (pintype "unspecified"))
      (node (ref "U6") (pin "2") (pinfunction "DO（IO1）_2") (pintype "unspecified"))
    )
    (net (code "83") (name "RF_MOSI") (class "Default")
      (node (ref "CN6") (pin "5") (pinfunction "5_5") (pintype "unspecified"))
      (node (ref "U11") (pin "36") (pinfunction "PB15_36") (pintype "unspecified"))
      (node (ref "U6") (pin "5") (pinfunction "DI（IO0）_5") (pintype "unspecified"))
    )
    (net (code "84") (name "RF_SCLK") (class "Default")
      (node (ref "CN6") (pin "4") (pinfunction "4_4") (pintype "unspecified"))
      (node (ref "U11") (pin "34") (pinfunction "PB13_34") (pintype "unspecified"))
      (node (ref "U6") (pin "6") (pinfunction "CLK_6") (pintype "unspecified"))
    )
    (net (code "85") (name "S_ADJ") (class "Default")
      (node (ref "C56") (pin "2") (pinfunction "2_2") (pintype "input"))
      (node (ref "R41") (pin "2") (pinfunction "2_2") (pintype "input"))
      (node (ref "U11") (pin "25") (pinfunction "PC5_25") (pintype "unspecified"))
    )
    (net (code "86") (name "S_INT") (class "Default")
      (node (ref "U11") (pin "57") (pinfunction "PB5_57") (pintype "unspecified"))
      (node (ref "U5") (pin "12") (pinfunction "INT_12") (pintype "unspecified"))
    )
    (net (code "87") (name "S_SCL") (class "Default")
      (node (ref "R17") (pin "1") (pinfunction "1_1") (pintype "input"))
      (node (ref "U11") (pin "58") (pinfunction "PB6_58") (pintype "unspecified"))
      (node (ref "U5") (pin "24") (pinfunction "SDA_24") (pintype "unspecified"))
    )
    (net (code "88") (name "S_SDA") (class "Default")
      (node (ref "R18") (pin "1") (pinfunction "1_1") (pintype "input"))
      (node (ref "U11") (pin "59") (pinfunction "PB7_59") (pintype "unspecified"))
      (node (ref "U5") (pin "23") (pinfunction "SCL_23") (pintype "unspecified"))
    )
    (net (code "89") (name "TIMA_CH1") (class "Default")
      (node (ref "U11") (pin "14") (pinfunction "PA0-WKUP_14") (pintype "unspecified"))
      (node (ref "U2") (pin "3") (pinfunction "IN1_3") (pintype "unspecified"))
    )
    (net (code "90") (name "TIMA_CH2") (class "Default")
      (node (ref "U11") (pin "15") (pinfunction "PA1_15") (pintype "unspecified"))
      (node (ref "U2") (pin "2") (pinfunction "IN2_2") (pintype "unspecified"))
    )
    (net (code "91") (name "TIMB_CH1") (class "Default")
      (node (ref "U11") (pin "16") (pinfunction "PA2_16") (pintype "unspecified"))
      (node (ref "U4") (pin "3") (pinfunction "IN1_3") (pintype "unspecified"))
    )
    (net (code "92") (name "TIMB_CH2") (class "Default")
      (node (ref "U11") (pin "17") (pinfunction "PA3_17") (pintype "unspecified"))
      (node (ref "U4") (pin "2") (pinfunction "IN2_2") (pintype "unspecified"))
    )
    (net (code "93") (name "TIMC_CH1") (class "Default")
      (node (ref "U11") (pin "20") (pinfunction "PA4_20") (pintype "unspecified"))
      (node (ref "U3") (pin "3") (pinfunction "IN1_3") (pintype "unspecified"))
    )
    (net (code "94") (name "TIMC_CH2") (class "Default")
      (node (ref "U11") (pin "21") (pinfunction "PA5_21") (pintype "unspecified"))
      (node (ref "U3") (pin "2") (pinfunction "IN2_2") (pintype "unspecified"))
    )
    (net (code "95") (name "TIMD_CH1") (class "Default")
      (node (ref "U1") (pin "3") (pinfunction "IN1_3") (pintype "unspecified"))
      (node (ref "U11") (pin "22") (pinfunction "PA6_22") (pintype "unspecified"))
    )
    (net (code "96") (name "TIMD_CH2") (class "Default")
      (node (ref "U1") (pin "2") (pinfunction "IN2_2") (pintype "unspecified"))
      (node (ref "U11") (pin "23") (pinfunction "PA7_23") (pintype "unspecified"))
    )
    (net (code "97") (name "USB_DN") (class "Default")
      (node (ref "U11") (pin "44") (pinfunction "PA11_44") (pintype "unspecified"))
      (node (ref "USB1") (pin "5") (pinfunction "DN2_5") (pintype "unspecified"))
      (node (ref "USB1") (pin "7") (pinfunction "DN1_7") (pintype "unspecified"))
    )
    (net (code "98") (name "USB_DP") (class "Default")
      (node (ref "U11") (pin "45") (pinfunction "PA12_45") (pintype "unspecified"))
      (node (ref "USB1") (pin "6") (pinfunction "DP1_6") (pintype "unspecified"))
      (node (ref "USB1") (pin "8") (pinfunction "DP2_8") (pintype "unspecified"))
    )
    (net (code "99") (name "USR_LED1") (class "Default")
      (node (ref "LED2") (pin "1") (pinfunction "C_1") (pintype "input"))
      (node (ref "U11") (pin "53") (pinfunction "PC12_53") (pintype "unspecified"))
    )
    (net (code "100") (name "USR_LED2") (class "Default")
      (node (ref "LED3") (pin "1") (pinfunction "C_1") (pintype "input"))
      (node (ref "U11") (pin "2") (pinfunction "PC13-TAMPER-RTC_2") (pintype "unspecified"))
    )
    (net (code "101") (name "USR_LED3") (class "Default")
      (node (ref "LED4") (pin "1") (pinfunction "C_1") (pintype "input"))
      (node (ref "U11") (pin "3") (pinfunction "PC14-OSC32_IN_3") (pintype "unspecified"))
    )
    (net (code "102") (name "USR_LED4") (class "Default")
      (node (ref "LED5") (pin "1") (pinfunction "C_1") (pintype "input"))
      (node (ref "U11") (pin "4") (pinfunction "PC15-OSC32_OUT_4") (pintype "unspecified"))
    )
    (net (code "103") (name "VBAT") (class "Default")
      (node (ref "C16") (pin "1") (pinfunction "1_1") (pintype "input"))
      (node (ref "C17") (pin "2") (pinfunction "2_2") (pintype "input"))
      (node (ref "C19") (pin "1") (pinfunction "1_1") (pintype "input"))
      (node (ref "C20") (pin "2") (pinfunction "2_2") (pintype "input"))
      (node (ref "C22") (pin "1") (pinfunction "1_1") (pintype "input"))
      (node (ref "C23") (pin "2") (pinfunction "2_2") (pintype "input"))
      (node (ref "C25") (pin "1") (pinfunction "1_1") (pintype "input"))
      (node (ref "C26") (pin "2") (pinfunction "2_2") (pintype "input"))
      (node (ref "CN7") (pin "1") (pinfunction "1_1") (pintype "unspecified"))
      (node (ref "D5") (pin "2") (pinfunction "A_2") (pintype "unspecified"))
      (node (ref "R31") (pin "1") (pinfunction "1_1") (pintype "input"))
      (node (ref "R33") (pin "2") (pinfunction "2_2") (pintype "input"))
      (node (ref "U1") (pin "5") (pinfunction "VM_5") (pintype "unspecified"))
      (node (ref "U2") (pin "5") (pinfunction "VM_5") (pintype "unspecified"))
      (node (ref "U3") (pin "5") (pinfunction "VM_5") (pintype "unspecified"))
      (node (ref "U4") (pin "5") (pinfunction "VM_5") (pintype "unspecified"))
    )
    (net (code "104") (name "VBUS") (class "Default")
      (node (ref "D7") (pin "2") (pinfunction "A_2") (pintype "unspecified"))
      (node (ref "USB1") (pin "11") (pinfunction "VBUS_11") (pintype "unspecified"))
      (node (ref "USB1") (pin "2") (pinfunction "VBUS_2") (pintype "unspecified"))
    )
    (net (code "105") (name "VDD") (class "Default")
      (node (ref "C1") (pin "2") (pinfunction "2_2") (pintype "input"))
      (node (ref "C15") (pin "2") (pinfunction "2_2") (pintype "input"))
      (node (ref "C18") (pin "2") (pinfunction "2_2") (pintype "input"))
      (node (ref "C2") (pin "2") (pinfunction "2_2") (pintype "input"))
      (node (ref "C21") (pin "2") (pinfunction "2_2") (pintype "input"))
      (node (ref "C24") (pin "2") (pinfunction "2_2") (pintype "input"))
      (node (ref "C28") (pin "1") (pinfunction "1_1") (pintype "input"))
      (node (ref "C29") (pin "1") (pinfunction "1_1") (pintype "input"))
      (node (ref "C30") (pin "1") (pinfunction "1_1") (pintype "input"))
      (node (ref "C33") (pin "2") (pinfunction "2_2") (pintype "input"))
      (node (ref "C34") (pin "1") (pinfunction "1_1") (pintype "input"))
      (node (ref "C36") (pin "1") (pinfunction "1_1") (pintype "input"))
      (node (ref "C38") (pin "2") (pinfunction "2_2") (pintype "input"))
      (node (ref "C39") (pin "2") (pinfunction "2_2") (pintype "input"))
      (node (ref "C47") (pin "1") (pinfunction "1_1") (pintype "input"))
      (node (ref "C49") (pin "1") (pinfunction "1_1") (pintype "input"))
      (node (ref "C51") (pin "1") (pinfunction "1_1") (pintype "input"))
      (node (ref "C54") (pin "1") (pinfunction "1_1") (pintype "input"))
      (node (ref "C59") (pin "1") (pinfunction "1_1") (pintype "input"))
      (node (ref "C60") (pin "1") (pinfunction "1_1") (pintype "input"))
      (node (ref "C61") (pin "1") (pinfunction "1_1") (pintype "input"))
      (node (ref "C62") (pin "1") (pinfunction "1_1") (pintype "input"))
      (node (ref "CN6") (pin "1") (pinfunction "1_1") (pintype "unspecified"))
      (node (ref "H1") (pin "1") (pinfunction "1_1") (pintype "unspecified"))
      (node (ref "H2") (pin "2") (pinfunction "2_2") (pintype "unspecified"))
      (node (ref "LED1") (pin "2") (pinfunction "A_2") (pintype "input"))
      (node (ref "PR1") (pin "2") (pinfunction "2_2") (pintype "input"))
      (node (ref "PR2") (pin "3") (pinfunction "3_3") (pintype "input"))
      (node (ref "R14") (pin "2") (pinfunction "2_2") (pintype "input"))
      (node (ref "R15") (pin "2") (pinfunction "2_2") (pintype "input"))
      (node (ref "R16") (pin "2") (pinfunction "2_2") (pintype "input"))
      (node (ref "R17") (pin "2") (pinfunction "2_2") (pintype "input"))
      (node (ref "R18") (pin "2") (pinfunction "2_2") (pintype "input"))
      (node (ref "R20") (pin "2") (pinfunction "2_2") (pintype "input"))
      (node (ref "R35") (pin "2") (pinfunction "2_2") (pintype "input"))
      (node (ref "R36") (pin "2") (pinfunction "2_2") (pintype "input"))
      (node (ref "R37") (pin "2") (pinfunction "2_2") (pintype "input"))
      (node (ref "R38") (pin "2") (pinfunction "2_2") (pintype "input"))
      (node (ref "R40") (pin "2") (pinfunction "2_2") (pintype "input"))
      (node (ref "R42") (pin "2") (pinfunction "2_2") (pintype "input"))
      (node (ref "RT1") (pin "1") (pinfunction "1_1") (pintype "input"))
      (node (ref "RT2") (pin "1") (pinfunction "1_1") (pintype "input"))
      (node (ref "RT3") (pin "1") (pinfunction "1_1") (pintype "input"))
      (node (ref "RT4") (pin "1") (pinfunction "1_1") (pintype "input"))
      (node (ref "U1") (pin "4") (pinfunction "VREF_4") (pintype "unspecified"))
      (node (ref "U10") (pin "5") (pinfunction "VOUT_5") (pintype "unspecified"))
      (node (ref "U11") (pin "1") (pinfunction "VBAT_1") (pintype "unspecified"))
      (node (ref "U11") (pin "19") (pinfunction "VDD_4_19") (pintype "unspecified"))
      (node (ref "U11") (pin "32") (pinfunction "VDD_1_32") (pintype "unspecified"))
      (node (ref "U11") (pin "48") (pinfunction "VDD_2_48") (pintype "unspecified"))
      (node (ref "U11") (pin "64") (pinfunction "VDD_3_64") (pintype "unspecified"))
      (node (ref "U12") (pin "8") (pinfunction "+V_8") (pintype "unspecified"))
      (node (ref "U13") (pin "8") (pinfunction "+V_8") (pintype "unspecified"))
      (node (ref "U14") (pin "8") (pinfunction "+V_8") (pintype "unspecified"))
      (node (ref "U2") (pin "4") (pinfunction "VREF_4") (pintype "unspecified"))
      (node (ref "U3") (pin "4") (pinfunction "VREF_4") (pintype "unspecified"))
      (node (ref "U4") (pin "4") (pinfunction "VREF_4") (pintype "unspecified"))
      (node (ref "U5") (pin "13") (pinfunction "VDD_13") (pintype "unspecified"))
      (node (ref "U5") (pin "8") (pinfunction "VLOGIC_8") (pintype "unspecified"))
      (node (ref "U6") (pin "3") (pinfunction "IO2_3") (pintype "unspecified"))
      (node (ref "U6") (pin "7") (pinfunction "IO3_7") (pintype "unspecified"))
      (node (ref "U6") (pin "8") (pinfunction "VCC_8") (pintype "unspecified"))
      (node (ref "U7") (pin "8") (pinfunction "VCC_8") (pintype "unspecified"))
      (node (ref "U8") (pin "5") (pinfunction "SHDN#_5") (pintype "unspecified"))
      (node (ref "U8") (pin "6") (pinfunction "VDD_6") (pintype "unspecified"))
    )
    (net (code "106") (name "unconnected-(U5-NC-Pad2)") (class "Default")
      (node (ref "U5") (pin "2") (pinfunction "NC_2") (pintype "unspecified+no_connect"))
    )
    (net (code "107") (name "unconnected-(U5-NC-Pad3)") (class "Default")
      (node (ref "U5") (pin "3") (pinfunction "NC_3") (pintype "unspecified+no_connect"))
    )
    (net (code "108") (name "unconnected-(U5-NC-Pad4)") (class "Default")
      (node (ref "U5") (pin "4") (pinfunction "NC_4") (pintype "unspecified+no_connect"))
    )
    (net (code "109") (name "unconnected-(U5-NC-Pad5)") (class "Default")
      (node (ref "U5") (pin "5") (pinfunction "NC_5") (pintype "unspecified+no_connect"))
    )
    (net (code "110") (name "unconnected-(U5-NC-Pad14)") (class "Default")
      (node (ref "U5") (pin "14") (pinfunction "NC_14") (pintype "unspecified+no_connect"))
    )
    (net (code "111") (name "unconnected-(U5-NC-Pad15)") (class "Default")
      (node (ref "U5") (pin "15") (pinfunction "NC_15") (pintype "unspecified+no_connect"))
    )
    (net (code "112") (name "unconnected-(U5-NC-Pad16)") (class "Default")
      (node (ref "U5") (pin "16") (pinfunction "NC_16") (pintype "unspecified+no_connect"))
    )
    (net (code "113") (name "unconnected-(U5-NC-Pad17)") (class "Default")
      (node (ref "U5") (pin "17") (pinfunction "NC_17") (pintype "unspecified+no_connect"))
    )
    (net (code "114") (name "unconnected-(U5-RESV-Pad19)") (class "Default")
      (node (ref "U5") (pin "19") (pinfunction "RESV_19") (pintype "unspecified+no_connect"))
    )
    (net (code "115") (name "unconnected-(U5-RESV-Pad21)") (class "Default")
      (node (ref "U5") (pin "21") (pinfunction "RESV_21") (pintype "unspecified+no_connect"))
    )
    (net (code "116") (name "unconnected-(U5-RESV-Pad22)") (class "Default")
      (node (ref "U5") (pin "22") (pinfunction "RESV_22") (pintype "unspecified+no_connect"))
    )
    (net (code "117") (name "unconnected-(U7-NC-Pad7)") (class "Default")
      (node (ref "U7") (pin "7") (pinfunction "NC_7") (pintype "unspecified+no_connect"))
    )
    (net (code "118") (name "unconnected-(U7-NC-Pad13)") (class "Default")
      (node (ref "U7") (pin "13") (pinfunction "NC_13") (pintype "unspecified+no_connect"))
    )
    (net (code "119") (name "unconnected-(U7-Reserved-Pad15)") (class "Default")
      (node (ref "U7") (pin "15") (pinfunction "Reserved_15") (pintype "unspecified+no_connect"))
    )
    (net (code "120") (name "unconnected-(U7-Reserved-Pad18)") (class "Default")
      (node (ref "U7") (pin "18") (pinfunction "Reserved_18") (pintype "unspecified+no_connect"))
    )
    (net (code "121") (name "unconnected-(U7-SCL-Pad17)") (class "Default")
      (node (ref "U7") (pin "17") (pinfunction "SCL_17") (pintype "unspecified+no_connect"))
    )
    (net (code "122") (name "unconnected-(U7-SDA-Pad16)") (class "Default")
      (node (ref "U7") (pin "16") (pinfunction "SDA_16") (pintype "unspecified+no_connect"))
    )
    (net (code "123") (name "unconnected-(U10-NC-Pad1)") (class "Default")
      (node (ref "U10") (pin "1") (pinfunction "NC_1") (pintype "unspecified+no_connect"))
    )
    (net (code "124") (name "unconnected-(U10-NC-Pad3)") (class "Default")
      (node (ref "U10") (pin "3") (pinfunction "NC_3") (pintype "unspecified+no_connect"))
    )
    (net (code "125") (name "unconnected-(U11-PB2-Pad28)") (class "Default")
      (node (ref "U11") (pin "28") (pinfunction "PB2_28") (pintype "unspecified+no_connect"))
    )
    (net (code "126") (name "unconnected-(U11-PB3-Pad55)") (class "Default")
      (node (ref "U11") (pin "55") (pinfunction "PB3_55") (pintype "unspecified+no_connect"))
    )
    (net (code "127") (name "unconnected-(U11-PB4-Pad56)") (class "Default")
      (node (ref "U11") (pin "56") (pinfunction "PB4_56") (pintype "unspecified+no_connect"))
    )
    (net (code "128") (name "unconnected-(U11-PB8-Pad61)") (class "Default")
      (node (ref "U11") (pin "61") (pinfunction "PB8_61") (pintype "unspecified+no_connect"))
    )
    (net (code "129") (name "unconnected-(U11-PB9-Pad62)") (class "Default")
      (node (ref "U11") (pin "62") (pinfunction "PB9_62") (pintype "unspecified+no_connect"))
    )
    (net (code "130") (name "unconnected-(U11-PC9-Pad40)") (class "Default")
      (node (ref "U11") (pin "40") (pinfunction "PC9_40") (pintype "unspecified+no_connect"))
    )
    (net (code "131") (name "unconnected-(U11-PC10-Pad51)") (class "Default")
      (node (ref "U11") (pin "51") (pinfunction "PC10_51") (pintype "unspecified+no_connect"))
    )
    (net (code "132") (name "unconnected-(U11-PC11-Pad52)") (class "Default")
      (node (ref "U11") (pin "52") (pinfunction "PC11_52") (pintype "unspecified+no_connect"))
    )
    (net (code "133") (name "unconnected-(U11-PD2-Pad54)") (class "Default")
      (node (ref "U11") (pin "54") (pinfunction "PD2_54") (pintype "unspecified+no_connect"))
    )
    (net (code "134") (name "unconnected-(USB1-SBU1-Pad9)") (class "Default")
      (node (ref "USB1") (pin "9") (pinfunction "SBU1_9") (pintype "unspecified+no_connect"))
    )
    (net (code "135") (name "unconnected-(USB1-SBU2-Pad3)") (class "Default")
      (node (ref "USB1") (pin "3") (pinfunction "SBU2_3") (pintype "unspecified+no_connect"))
    )
  )
)
